# Unitbase_Keinz_2022.net
KiCad netlist of a schematic drawn in EAGLE
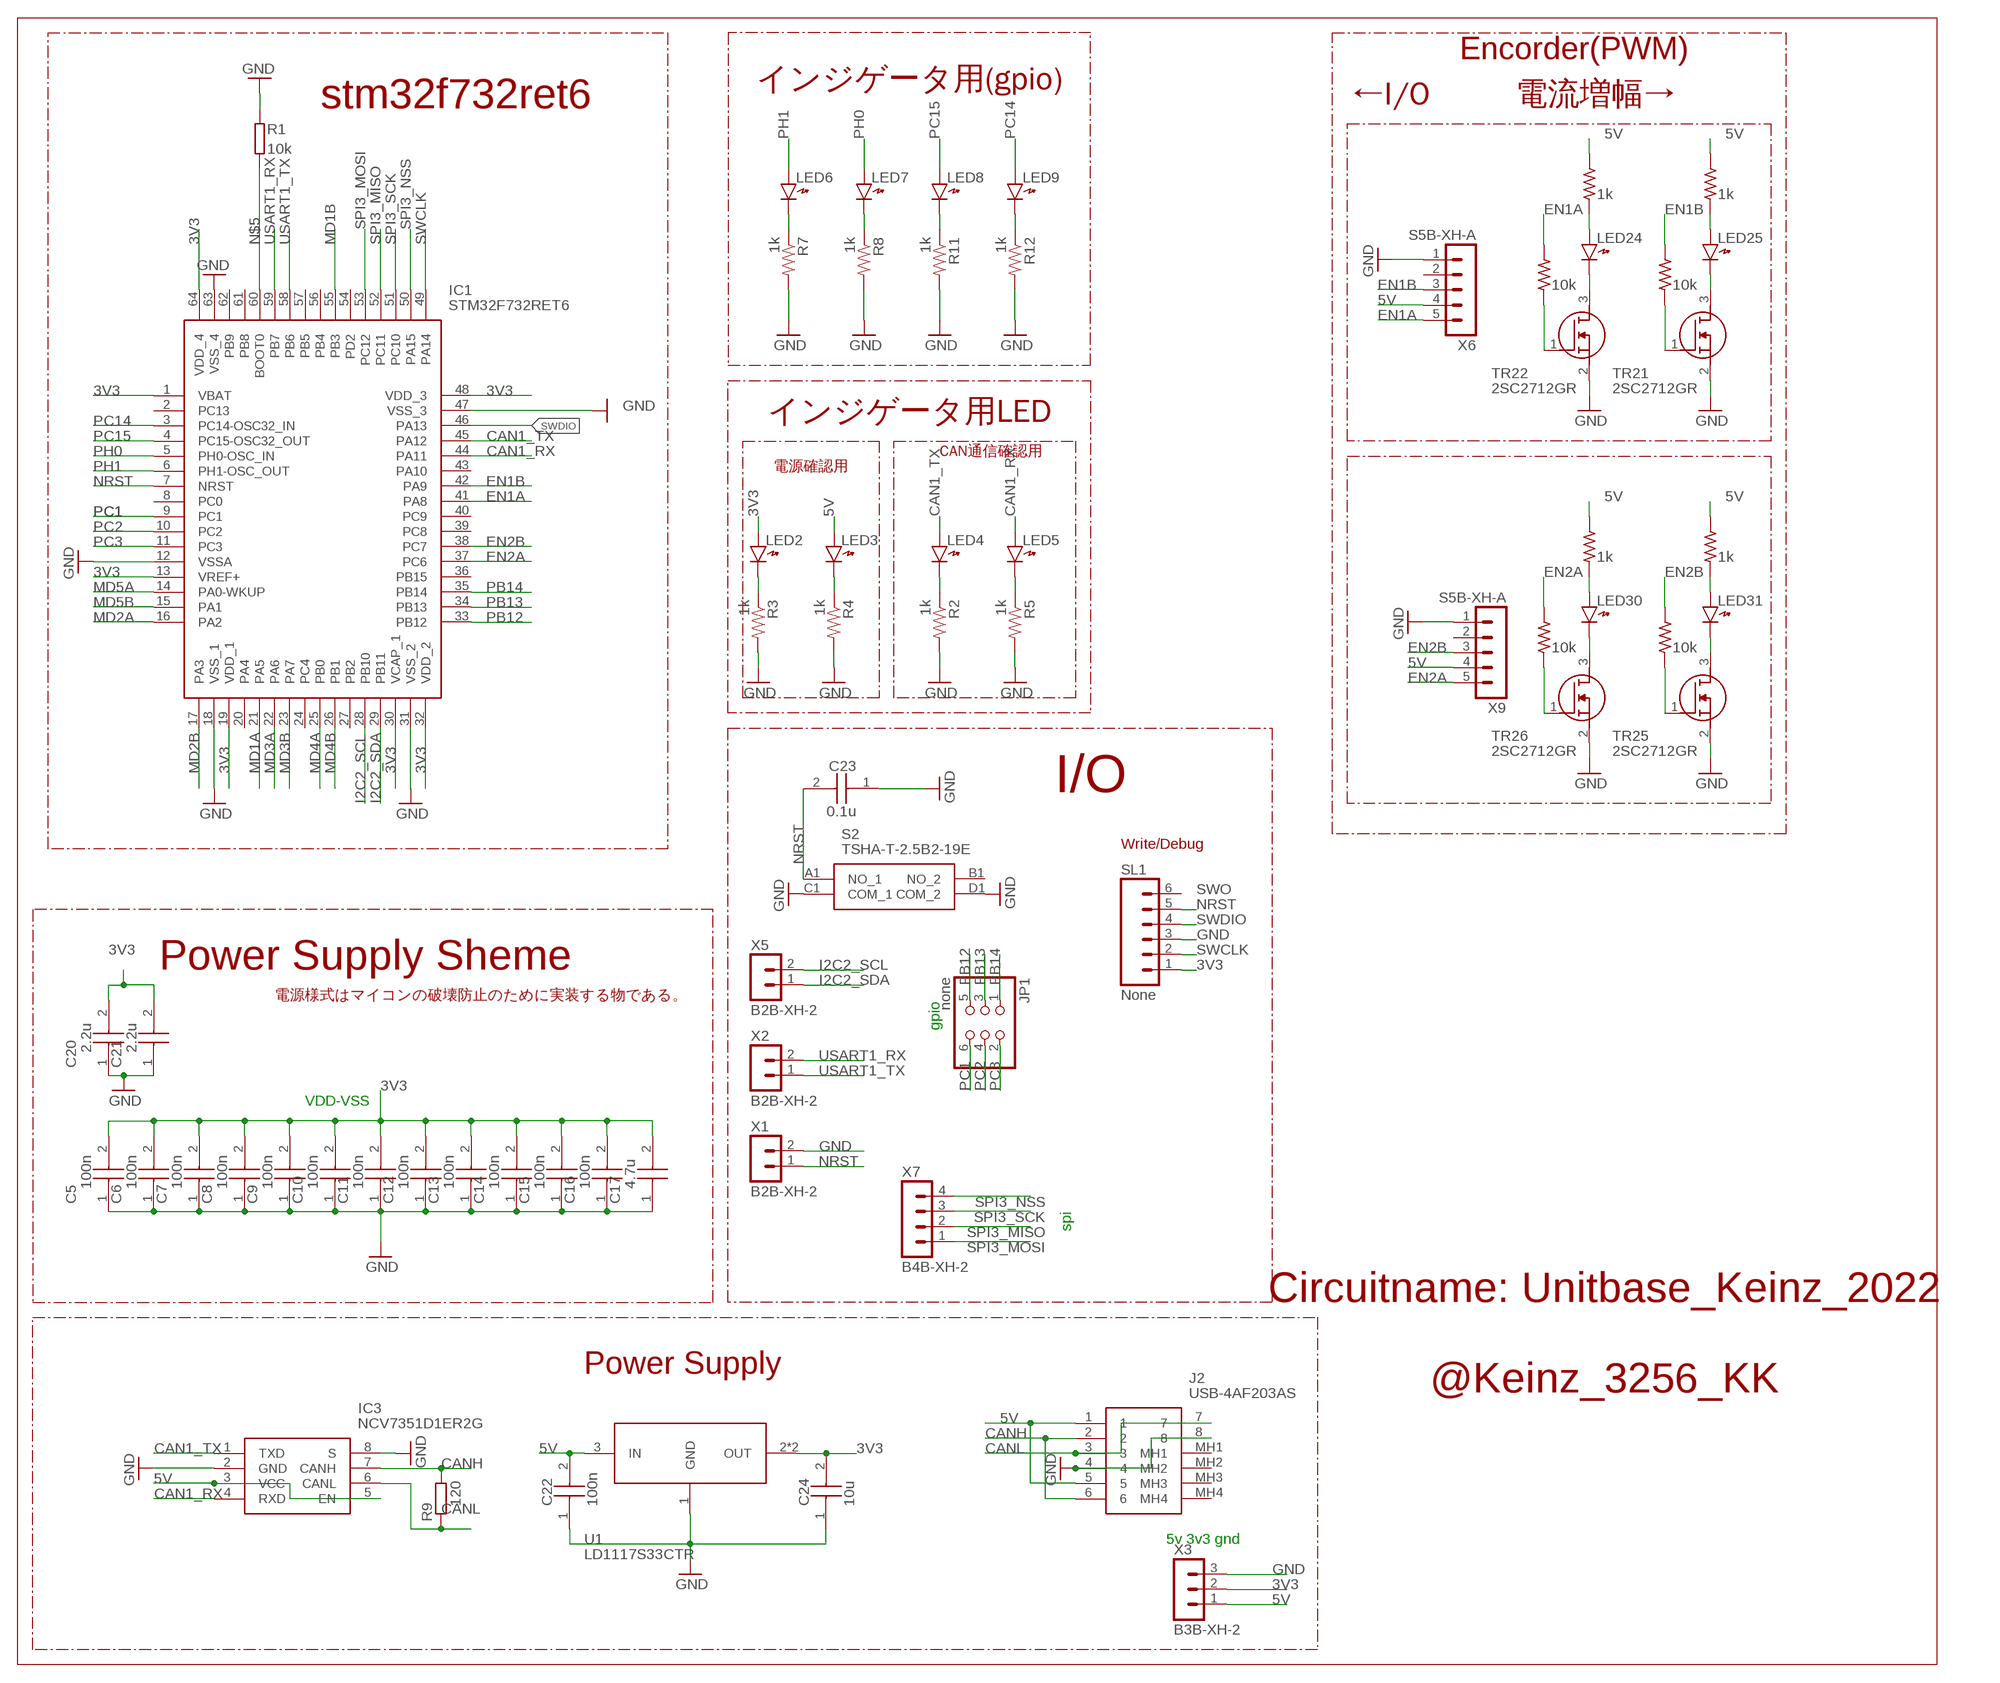
[diagram p0: schematic, sheet 1]
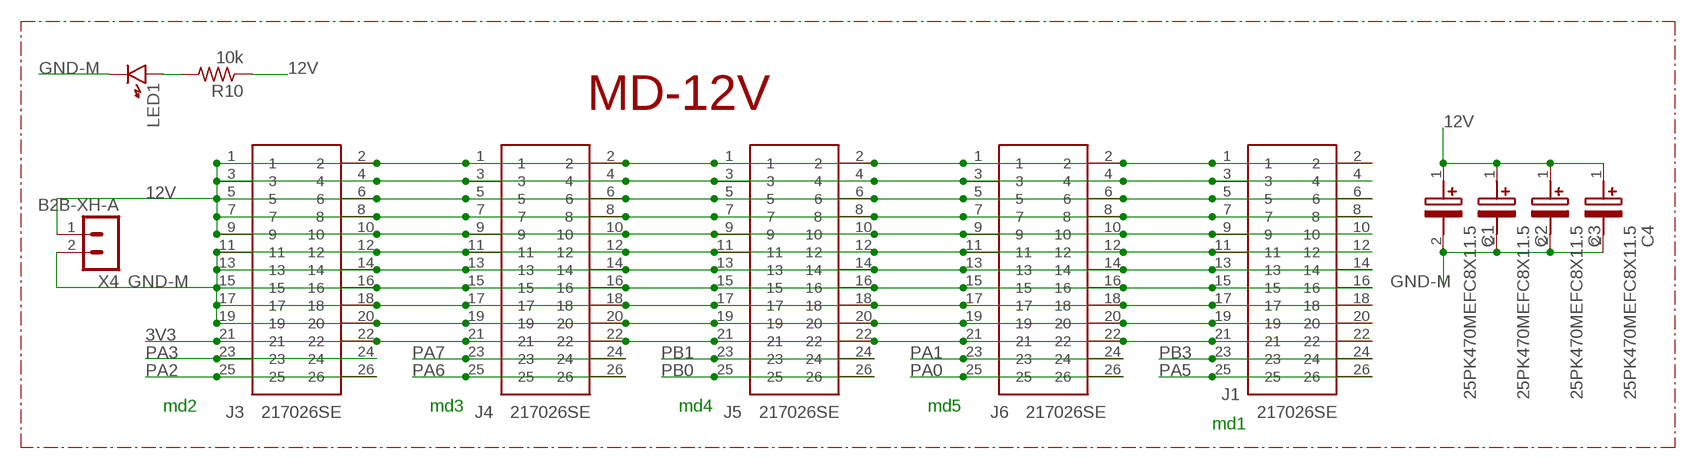
[diagram p1: schematic, sheet 2]
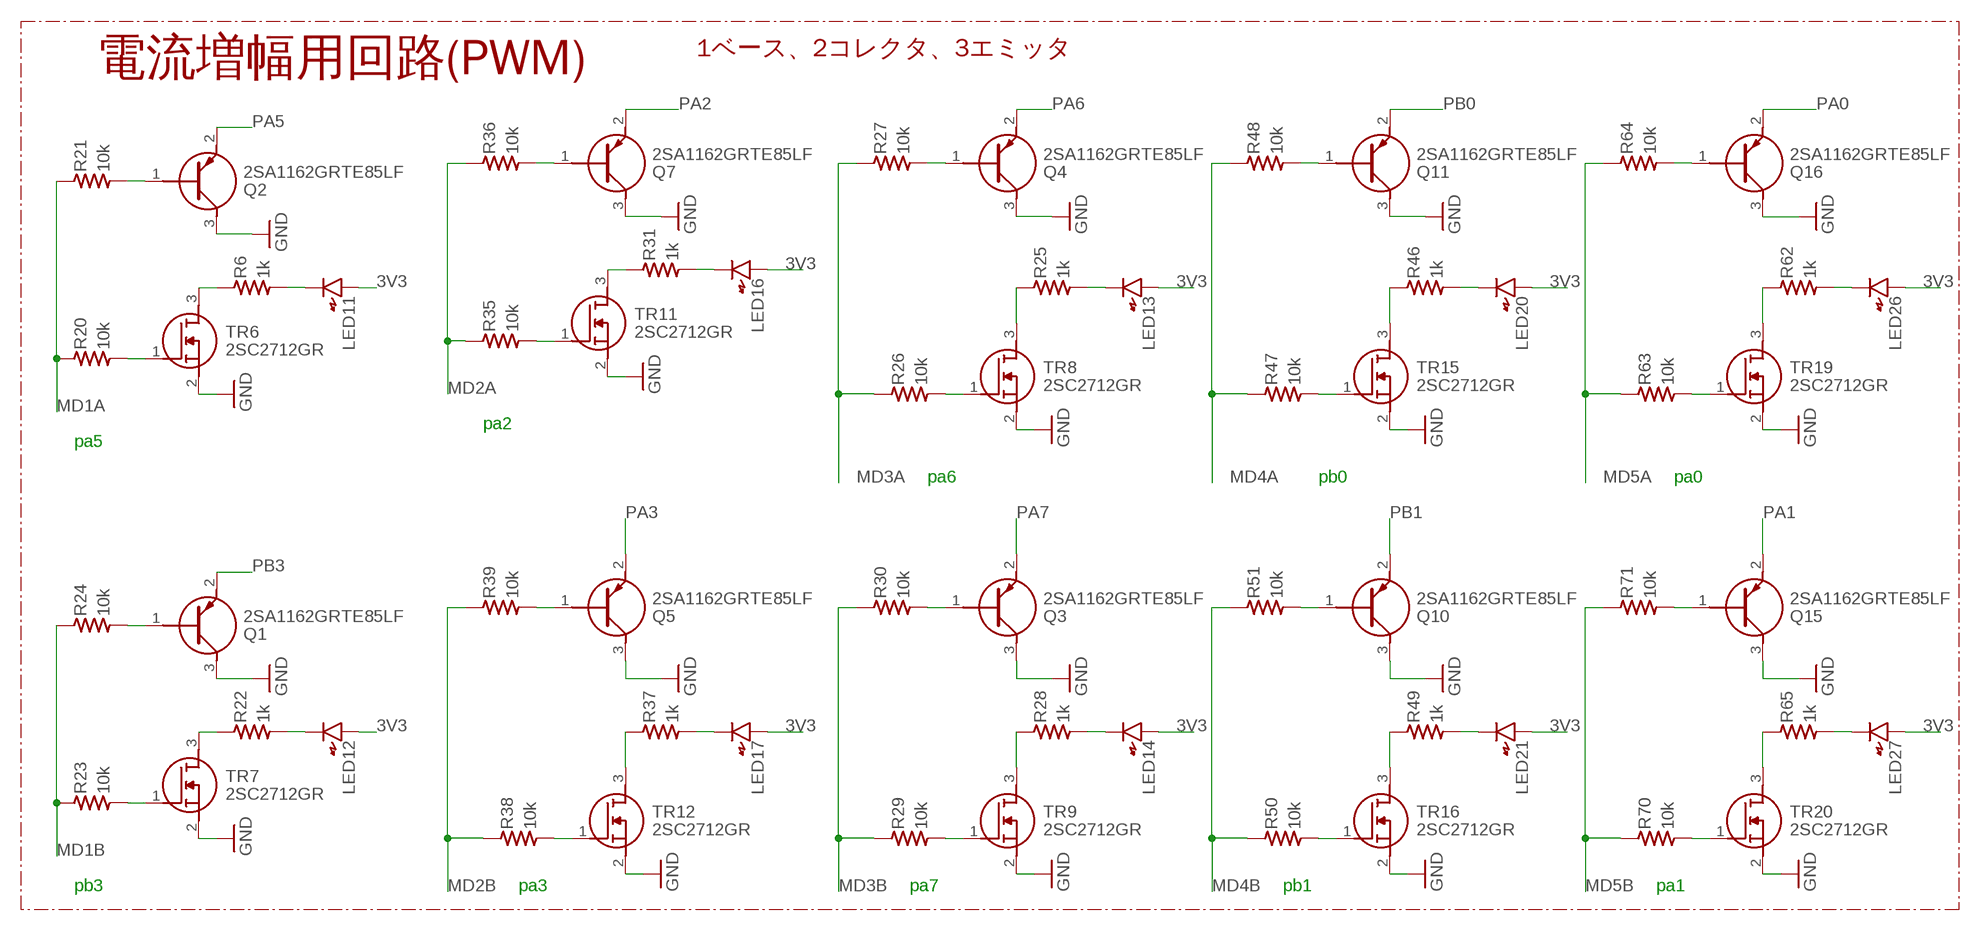
[diagram p2: schematic, sheet 3]

(export (version "E")
  (design (tool "Eeschema 10.0.6"))
  (components
    (comp (ref "C1")
      (value "25PK470MEFC8X11.5")
      (footprint "eagle-import:CAPPRD350W60D825H1150")
      (fields (field (name "MOUSER_PART_NUMBER") "232-25PK470MEFC8X115"))
      (libsource (lib "eagle-import") (part "25PK470MEFC8X11.5"))
    )
    (comp (ref "C2")
      (value "25PK470MEFC8X11.5")
      (footprint "eagle-import:CAPPRD350W60D825H1150")
      (fields (field (name "MOUSER_PART_NUMBER") "232-25PK470MEFC8X115"))
      (libsource (lib "eagle-import") (part "25PK470MEFC8X11.5"))
    )
    (comp (ref "C3")
      (value "25PK470MEFC8X11.5")
      (footprint "eagle-import:CAPPRD350W60D825H1150")
      (fields (field (name "MOUSER_PART_NUMBER") "232-25PK470MEFC8X115"))
      (libsource (lib "eagle-import") (part "25PK470MEFC8X11.5"))
    )
    (comp (ref "C4")
      (value "25PK470MEFC8X11.5")
      (footprint "eagle-import:CAPPRD350W60D825H1150")
      (fields (field (name "MOUSER_PART_NUMBER") "232-25PK470MEFC8X115"))
      (libsource (lib "eagle-import") (part "25PK470MEFC8X11.5"))
    )
    (comp (ref "J1")
      (value "217026SE")
      (footprint "eagle-import:217026SE")
      (libsource (lib "eagle-import") (part "217026SE"))
    )
    (comp (ref "J3")
      (value "217026SE")
      (footprint "eagle-import:217026SE")
      (libsource (lib "eagle-import") (part "217026SE"))
    )
    (comp (ref "J4")
      (value "217026SE")
      (footprint "eagle-import:217026SE")
      (libsource (lib "eagle-import") (part "217026SE"))
    )
    (comp (ref "J5")
      (value "217026SE")
      (footprint "eagle-import:217026SE")
      (libsource (lib "eagle-import") (part "217026SE"))
    )
    (comp (ref "J6")
      (value "217026SE")
      (footprint "eagle-import:217026SE")
      (libsource (lib "eagle-import") (part "217026SE"))
    )
    (comp (ref "LED1")
      (value "LED1608")
      (footprint "eagle-import:LED1608")
      (libsource (lib "eagle-import") (part "LED1608"))
    )
    (comp (ref "R10")
      (value "10k")
      (footprint "eagle-import:R0603")
      (libsource (lib "eagle-import") (part "R-US_R0603"))
    )
    (comp (ref "X4")
      (value "B2B-XH-A")
      (footprint "eagle-import:B2B-XH-A")
      (libsource (lib "eagle-import") (part "B2B-XH-A"))
    )
    (comp (ref "C5")
      (value "100n")
      (footprint "eagle-import:CAPC1709X100N")
      (fields
        (field (name "MANUFACTURER_PART_NUMBER") "AMK107BBJ476MA-RE")
        (field (name "MOUSER_PART_NUMBER") "963-AMK107BBJ476MARE")
        (field (name "RS_PART_NUMBER") "1843762P")
      )
      (libsource (lib "eagle-import") (part "AMK107BBJ476MA-RE"))
    )
    (comp (ref "C6")
      (value "100n")
      (footprint "eagle-import:CAPC1709X100N")
      (fields
        (field (name "MANUFACTURER_PART_NUMBER") "AMK107BBJ476MA-RE")
        (field (name "MOUSER_PART_NUMBER") "963-AMK107BBJ476MARE")
        (field (name "RS_PART_NUMBER") "1843762P")
      )
      (libsource (lib "eagle-import") (part "AMK107BBJ476MA-RE"))
    )
    (comp (ref "C7")
      (value "100n")
      (footprint "eagle-import:CAPC1709X100N")
      (fields
        (field (name "MANUFACTURER_PART_NUMBER") "AMK107BBJ476MA-RE")
        (field (name "MOUSER_PART_NUMBER") "963-AMK107BBJ476MARE")
        (field (name "RS_PART_NUMBER") "1843762P")
      )
      (libsource (lib "eagle-import") (part "AMK107BBJ476MA-RE"))
    )
    (comp (ref "C8")
      (value "100n")
      (footprint "eagle-import:CAPC1709X100N")
      (fields
        (field (name "MANUFACTURER_PART_NUMBER") "AMK107BBJ476MA-RE")
        (field (name "MOUSER_PART_NUMBER") "963-AMK107BBJ476MARE")
        (field (name "RS_PART_NUMBER") "1843762P")
      )
      (libsource (lib "eagle-import") (part "AMK107BBJ476MA-RE"))
    )
    (comp (ref "C9")
      (value "100n")
      (footprint "eagle-import:CAPC1709X100N")
      (fields
        (field (name "MANUFACTURER_PART_NUMBER") "AMK107BBJ476MA-RE")
        (field (name "MOUSER_PART_NUMBER") "963-AMK107BBJ476MARE")
        (field (name "RS_PART_NUMBER") "1843762P")
      )
      (libsource (lib "eagle-import") (part "AMK107BBJ476MA-RE"))
    )
    (comp (ref "C10")
      (value "100n")
      (footprint "eagle-import:CAPC1709X100N")
      (fields
        (field (name "MANUFACTURER_PART_NUMBER") "AMK107BBJ476MA-RE")
        (field (name "MOUSER_PART_NUMBER") "963-AMK107BBJ476MARE")
        (field (name "RS_PART_NUMBER") "1843762P")
      )
      (libsource (lib "eagle-import") (part "AMK107BBJ476MA-RE"))
    )
    (comp (ref "C11")
      (value "100n")
      (footprint "eagle-import:CAPC1709X100N")
      (fields
        (field (name "MANUFACTURER_PART_NUMBER") "AMK107BBJ476MA-RE")
        (field (name "MOUSER_PART_NUMBER") "963-AMK107BBJ476MARE")
        (field (name "RS_PART_NUMBER") "1843762P")
      )
      (libsource (lib "eagle-import") (part "AMK107BBJ476MA-RE"))
    )
    (comp (ref "C12")
      (value "100n")
      (footprint "eagle-import:CAPC1709X100N")
      (fields
        (field (name "MANUFACTURER_PART_NUMBER") "AMK107BBJ476MA-RE")
        (field (name "MOUSER_PART_NUMBER") "963-AMK107BBJ476MARE")
        (field (name "RS_PART_NUMBER") "1843762P")
      )
      (libsource (lib "eagle-import") (part "AMK107BBJ476MA-RE"))
    )
    (comp (ref "C13")
      (value "100n")
      (footprint "eagle-import:CAPC1709X100N")
      (fields
        (field (name "MANUFACTURER_PART_NUMBER") "AMK107BBJ476MA-RE")
        (field (name "MOUSER_PART_NUMBER") "963-AMK107BBJ476MARE")
        (field (name "RS_PART_NUMBER") "1843762P")
      )
      (libsource (lib "eagle-import") (part "AMK107BBJ476MA-RE"))
    )
    (comp (ref "C14")
      (value "100n")
      (footprint "eagle-import:CAPC1709X100N")
      (fields
        (field (name "MANUFACTURER_PART_NUMBER") "AMK107BBJ476MA-RE")
        (field (name "MOUSER_PART_NUMBER") "963-AMK107BBJ476MARE")
        (field (name "RS_PART_NUMBER") "1843762P")
      )
      (libsource (lib "eagle-import") (part "AMK107BBJ476MA-RE"))
    )
    (comp (ref "C15")
      (value "100n")
      (footprint "eagle-import:CAPC1709X100N")
      (fields
        (field (name "MANUFACTURER_PART_NUMBER") "AMK107BBJ476MA-RE")
        (field (name "MOUSER_PART_NUMBER") "963-AMK107BBJ476MARE")
        (field (name "RS_PART_NUMBER") "1843762P")
      )
      (libsource (lib "eagle-import") (part "AMK107BBJ476MA-RE"))
    )
    (comp (ref "C16")
      (value "100n")
      (footprint "eagle-import:CAPC1709X100N")
      (fields
        (field (name "MANUFACTURER_PART_NUMBER") "AMK107BBJ476MA-RE")
        (field (name "MOUSER_PART_NUMBER") "963-AMK107BBJ476MARE")
        (field (name "RS_PART_NUMBER") "1843762P")
      )
      (libsource (lib "eagle-import") (part "AMK107BBJ476MA-RE"))
    )
    (comp (ref "C17")
      (value "4.7u")
      (footprint "eagle-import:CAPC1709X100N")
      (fields
        (field (name "MANUFACTURER_PART_NUMBER") "AMK107BBJ476MA-RE")
        (field (name "MOUSER_PART_NUMBER") "963-AMK107BBJ476MARE")
        (field (name "RS_PART_NUMBER") "1843762P")
      )
      (libsource (lib "eagle-import") (part "AMK107BBJ476MA-RE"))
    )
    (comp (ref "C20")
      (value "2.2u")
      (footprint "eagle-import:CAPC1709X100N")
      (fields
        (field (name "MANUFACTURER_PART_NUMBER") "AMK107BBJ476MA-RE")
        (field (name "MOUSER_PART_NUMBER") "963-AMK107BBJ476MARE")
        (field (name "RS_PART_NUMBER") "1843762P")
      )
      (libsource (lib "eagle-import") (part "AMK107BBJ476MA-RE"))
    )
    (comp (ref "C21")
      (value "2.2u")
      (footprint "eagle-import:CAPC1709X100N")
      (fields
        (field (name "MANUFACTURER_PART_NUMBER") "AMK107BBJ476MA-RE")
        (field (name "MOUSER_PART_NUMBER") "963-AMK107BBJ476MARE")
        (field (name "RS_PART_NUMBER") "1843762P")
      )
      (libsource (lib "eagle-import") (part "AMK107BBJ476MA-RE"))
    )
    (comp (ref "C22")
      (value "100n")
      (footprint "eagle-import:CAPC1608X90N")
      (fields
        (field (name "MANUFACTURER_PART_NUMBER") "GRM188B31A106KE69D")
        (field (name "RS_PART_NUMBER") "8847157P")
      )
      (libsource (lib "eagle-import") (part "GRM188B31A106KE69D"))
    )
    (comp (ref "C23")
      (value "0.1u")
      (footprint "eagle-import:CAPC1709X100N")
      (fields
        (field (name "MANUFACTURER_PART_NUMBER") "AMK107BBJ476MA-RE")
        (field (name "MOUSER_PART_NUMBER") "963-AMK107BBJ476MARE")
        (field (name "RS_PART_NUMBER") "1843762P")
      )
      (libsource (lib "eagle-import") (part "AMK107BBJ476MA-RE"))
    )
    (comp (ref "C24")
      (value "10u")
      (footprint "eagle-import:CAPC1608X90N")
      (fields
        (field (name "MANUFACTURER_PART_NUMBER") "GRM188B31A106KE69D")
        (field (name "RS_PART_NUMBER") "8847157P")
      )
      (libsource (lib "eagle-import") (part "GRM188B31A106KE69D"))
    )
    (comp (ref "IC1")
      (value "STM32F732RET6")
      (footprint "eagle-import:QFP50P1200X1200X160-64N@1")
      (fields (field (name "MOUSER_PART_NUMBER") "511-STM32F732RET6"))
      (libsource (lib "eagle-import") (part "STM32F732RET6"))
    )
    (comp (ref "IC3")
      (value "NCV7351D1ER2G")
      (footprint "eagle-import:SOIC127P600X175-8N")
      (fields (field (name "MOUSER_PART_NUMBER") "863-NCV7351D1ER2G"))
      (libsource (lib "eagle-import") (part "NCV7351D1ER2G"))
    )
    (comp (ref "J2")
      (value "USB-4AF203AS")
      (footprint "eagle-import:USB4AF203AS")
      (libsource (lib "eagle-import") (part "USB-4AF203AS"))
    )
    (comp (ref "JP1")
      (value "none")
      (footprint "eagle-import:2X03")
      (libsource (lib "eagle-import") (part "PINHD-2X3"))
    )
    (comp (ref "LED2")
      (value "LED1608")
      (footprint "eagle-import:LED1608")
      (libsource (lib "eagle-import") (part "LED1608"))
    )
    (comp (ref "LED3")
      (value "LED1608")
      (footprint "eagle-import:LED1608")
      (libsource (lib "eagle-import") (part "LED1608"))
    )
    (comp (ref "LED4")
      (value "LED1608")
      (footprint "eagle-import:LED1608")
      (libsource (lib "eagle-import") (part "LED1608"))
    )
    (comp (ref "LED5")
      (value "LED1608")
      (footprint "eagle-import:LED1608")
      (libsource (lib "eagle-import") (part "LED1608"))
    )
    (comp (ref "LED6")
      (value "LED1608")
      (footprint "eagle-import:LED1608")
      (libsource (lib "eagle-import") (part "LED1608"))
    )
    (comp (ref "LED7")
      (value "LED1608")
      (footprint "eagle-import:LED1608")
      (libsource (lib "eagle-import") (part "LED1608"))
    )
    (comp (ref "LED8")
      (value "LED1608")
      (footprint "eagle-import:LED1608")
      (libsource (lib "eagle-import") (part "LED1608"))
    )
    (comp (ref "LED9")
      (value "LED1608")
      (footprint "eagle-import:LED1608")
      (libsource (lib "eagle-import") (part "LED1608"))
    )
    (comp (ref "LED24")
      (value "LED1608")
      (footprint "eagle-import:LED1608")
      (libsource (lib "eagle-import") (part "LED1608"))
    )
    (comp (ref "LED25")
      (value "LED1608")
      (footprint "eagle-import:LED1608")
      (libsource (lib "eagle-import") (part "LED1608"))
    )
    (comp (ref "LED30")
      (value "LED1608")
      (footprint "eagle-import:LED1608")
      (libsource (lib "eagle-import") (part "LED1608"))
    )
    (comp (ref "LED31")
      (value "LED1608")
      (footprint "eagle-import:LED1608")
      (libsource (lib "eagle-import") (part "LED1608"))
    )
    (comp (ref "R1")
      (value "10k")
      (footprint "eagle-import:SMD1608")
      (libsource (lib "eagle-import") (part "RESISTOR1608"))
    )
    (comp (ref "R2")
      (value "1k")
      (footprint "eagle-import:R0603")
      (libsource (lib "eagle-import") (part "R-US_R0603"))
    )
    (comp (ref "R3")
      (value "1k")
      (footprint "eagle-import:R0603")
      (libsource (lib "eagle-import") (part "R-US_R0603"))
    )
    (comp (ref "R4")
      (value "1k")
      (footprint "eagle-import:R0603")
      (libsource (lib "eagle-import") (part "R-US_R0603"))
    )
    (comp (ref "R5")
      (value "1k")
      (footprint "eagle-import:R0603")
      (libsource (lib "eagle-import") (part "R-US_R0603"))
    )
    (comp (ref "R7")
      (value "1k")
      (footprint "eagle-import:R0603")
      (libsource (lib "eagle-import") (part "R-US_R0603"))
    )
    (comp (ref "R8")
      (value "1k")
      (footprint "eagle-import:R0603")
      (libsource (lib "eagle-import") (part "R-US_R0603"))
    )
    (comp (ref "R9")
      (value "120")
      (footprint "eagle-import:1608")
      (libsource (lib "eagle-import") (part "R1608"))
    )
    (comp (ref "R11")
      (value "1k")
      (footprint "eagle-import:R0603")
      (libsource (lib "eagle-import") (part "R-US_R0603"))
    )
    (comp (ref "R12")
      (value "1k")
      (footprint "eagle-import:R0603")
      (libsource (lib "eagle-import") (part "R-US_R0603"))
    )
    (comp (ref "R54")
      (value "10k")
      (footprint "eagle-import:SMD1608")
      (libsource (lib "eagle-import") (part "RESISTOR-US1608"))
    )
    (comp (ref "R59")
      (value "1k")
      (footprint "eagle-import:SMD1608")
      (libsource (lib "eagle-import") (part "RESISTOR-US1608"))
    )
    (comp (ref "R60")
      (value "10k")
      (footprint "eagle-import:SMD1608")
      (libsource (lib "eagle-import") (part "RESISTOR-US1608"))
    )
    (comp (ref "R61")
      (value "1k")
      (footprint "eagle-import:SMD1608")
      (libsource (lib "eagle-import") (part "RESISTOR-US1608"))
    )
    (comp (ref "R66")
      (value "10k")
      (footprint "eagle-import:SMD1608")
      (libsource (lib "eagle-import") (part "RESISTOR-US1608"))
    )
    (comp (ref "R67")
      (value "1k")
      (footprint "eagle-import:SMD1608")
      (libsource (lib "eagle-import") (part "RESISTOR-US1608"))
    )
    (comp (ref "R68")
      (value "10k")
      (footprint "eagle-import:SMD1608")
      (libsource (lib "eagle-import") (part "RESISTOR-US1608"))
    )
    (comp (ref "R69")
      (value "1k")
      (footprint "eagle-import:SMD1608")
      (libsource (lib "eagle-import") (part "RESISTOR-US1608"))
    )
    (comp (ref "S2")
      (value "TSHA-T-2.5B2-19E")
      (footprint "eagle-import:TSHAT25B219E")
      (libsource (lib "eagle-import") (part "TSHA-T-2.5B2-19E"))
    )
    (comp (ref "SL1")
      (value "None")
      (footprint "eagle-import:06PA")
      (libsource (lib "eagle-import") (part "MA06"))
    )
    (comp (ref "TR21")
      (value "2SC2712GR")
      (footprint "eagle-import:SOT-23")
      (libsource (lib "eagle-import") (part "SOT-23_NMOS"))
    )
    (comp (ref "TR22")
      (value "2SC2712GR")
      (footprint "eagle-import:SOT-23")
      (libsource (lib "eagle-import") (part "SOT-23_NMOS"))
    )
    (comp (ref "TR25")
      (value "2SC2712GR")
      (footprint "eagle-import:SOT-23")
      (libsource (lib "eagle-import") (part "SOT-23_NMOS"))
    )
    (comp (ref "TR26")
      (value "2SC2712GR")
      (footprint "eagle-import:SOT-23")
      (libsource (lib "eagle-import") (part "SOT-23_NMOS"))
    )
    (comp (ref "U1")
      (value "LD1117S33CTR")
      (footprint "eagle-import:SOT223")
      (fields (field (name "MF") "STMicroelectronics"))
      (libsource (lib "eagle-import") (part "LD1117S33CTR"))
    )
    (comp (ref "X1")
      (value "B2B-XH-2")
      (footprint "eagle-import:B2B-XH-A")
      (libsource (lib "eagle-import") (part "B2B-XH-2"))
    )
    (comp (ref "X2")
      (value "B2B-XH-2")
      (footprint "eagle-import:B2B-XH-A")
      (libsource (lib "eagle-import") (part "B2B-XH-2"))
    )
    (comp (ref "X3")
      (value "B3B-XH-2")
      (footprint "eagle-import:B3B-XH-A")
      (libsource (lib "eagle-import") (part "B3B-XH-2"))
    )
    (comp (ref "X5")
      (value "B2B-XH-2")
      (footprint "eagle-import:B2B-XH-A")
      (libsource (lib "eagle-import") (part "B2B-XH-2"))
    )
    (comp (ref "X6")
      (value "S5B-XH-A")
      (footprint "eagle-import:S5B-XH-A")
      (libsource (lib "eagle-import") (part "S5B-XH-A"))
    )
    (comp (ref "X7")
      (value "B4B-XH-2")
      (footprint "eagle-import:B4B-XH-A")
      (libsource (lib "eagle-import") (part "B4B-XH-2"))
    )
    (comp (ref "X9")
      (value "S5B-XH-A")
      (footprint "eagle-import:S5B-XH-A")
      (libsource (lib "eagle-import") (part "S5B-XH-A"))
    )
    (comp (ref "LED11")
      (value "LED1608")
      (footprint "eagle-import:LED1608")
      (libsource (lib "eagle-import") (part "LED1608"))
    )
    (comp (ref "LED12")
      (value "LED1608")
      (footprint "eagle-import:LED1608")
      (libsource (lib "eagle-import") (part "LED1608"))
    )
    (comp (ref "LED13")
      (value "LED1608")
      (footprint "eagle-import:LED1608")
      (libsource (lib "eagle-import") (part "LED1608"))
    )
    (comp (ref "LED14")
      (value "LED1608")
      (footprint "eagle-import:LED1608")
      (libsource (lib "eagle-import") (part "LED1608"))
    )
    (comp (ref "LED16")
      (value "LED1608")
      (footprint "eagle-import:LED1608")
      (libsource (lib "eagle-import") (part "LED1608"))
    )
    (comp (ref "LED17")
      (value "LED1608")
      (footprint "eagle-import:LED1608")
      (libsource (lib "eagle-import") (part "LED1608"))
    )
    (comp (ref "LED20")
      (value "LED1608")
      (footprint "eagle-import:LED1608")
      (libsource (lib "eagle-import") (part "LED1608"))
    )
    (comp (ref "LED21")
      (value "LED1608")
      (footprint "eagle-import:LED1608")
      (libsource (lib "eagle-import") (part "LED1608"))
    )
    (comp (ref "LED26")
      (value "LED1608")
      (footprint "eagle-import:LED1608")
      (libsource (lib "eagle-import") (part "LED1608"))
    )
    (comp (ref "LED27")
      (value "LED1608")
      (footprint "eagle-import:LED1608")
      (libsource (lib "eagle-import") (part "LED1608"))
    )
    (comp (ref "Q1")
      (value "2SA1162GRTE85LF")
      (footprint "eagle-import:2SA1162GRTE85LF")
      (libsource (lib "eagle-import") (part "2SA1162GRTE85LF"))
    )
    (comp (ref "Q2")
      (value "2SA1162GRTE85LF")
      (footprint "eagle-import:2SA1162GRTE85LF")
      (libsource (lib "eagle-import") (part "2SA1162GRTE85LF"))
    )
    (comp (ref "Q3")
      (value "2SA1162GRTE85LF")
      (footprint "eagle-import:2SA1162GRTE85LF")
      (libsource (lib "eagle-import") (part "2SA1162GRTE85LF"))
    )
    (comp (ref "Q4")
      (value "2SA1162GRTE85LF")
      (footprint "eagle-import:2SA1162GRTE85LF")
      (libsource (lib "eagle-import") (part "2SA1162GRTE85LF"))
    )
    (comp (ref "Q5")
      (value "2SA1162GRTE85LF")
      (footprint "eagle-import:2SA1162GRTE85LF")
      (libsource (lib "eagle-import") (part "2SA1162GRTE85LF"))
    )
    (comp (ref "Q7")
      (value "2SA1162GRTE85LF")
      (footprint "eagle-import:2SA1162GRTE85LF")
      (libsource (lib "eagle-import") (part "2SA1162GRTE85LF"))
    )
    (comp (ref "Q10")
      (value "2SA1162GRTE85LF")
      (footprint "eagle-import:2SA1162GRTE85LF")
      (libsource (lib "eagle-import") (part "2SA1162GRTE85LF"))
    )
    (comp (ref "Q11")
      (value "2SA1162GRTE85LF")
      (footprint "eagle-import:2SA1162GRTE85LF")
      (libsource (lib "eagle-import") (part "2SA1162GRTE85LF"))
    )
    (comp (ref "Q15")
      (value "2SA1162GRTE85LF")
      (footprint "eagle-import:2SA1162GRTE85LF")
      (libsource (lib "eagle-import") (part "2SA1162GRTE85LF"))
    )
    (comp (ref "Q16")
      (value "2SA1162GRTE85LF")
      (footprint "eagle-import:2SA1162GRTE85LF")
      (libsource (lib "eagle-import") (part "2SA1162GRTE85LF"))
    )
    (comp (ref "R6")
      (value "1k")
      (footprint "eagle-import:SMD1608")
      (libsource (lib "eagle-import") (part "RESISTOR-US1608"))
    )
    (comp (ref "R20")
      (value "10k")
      (footprint "eagle-import:SMD1608")
      (libsource (lib "eagle-import") (part "RESISTOR-US1608"))
    )
    (comp (ref "R21")
      (value "10k")
      (footprint "eagle-import:SMD1608")
      (libsource (lib "eagle-import") (part "RESISTOR-US1608"))
    )
    (comp (ref "R22")
      (value "1k")
      (footprint "eagle-import:SMD1608")
      (libsource (lib "eagle-import") (part "RESISTOR-US1608"))
    )
    (comp (ref "R23")
      (value "10k")
      (footprint "eagle-import:SMD1608")
      (libsource (lib "eagle-import") (part "RESISTOR-US1608"))
    )
    (comp (ref "R24")
      (value "10k")
      (footprint "eagle-import:SMD1608")
      (libsource (lib "eagle-import") (part "RESISTOR-US1608"))
    )
    (comp (ref "R25")
      (value "1k")
      (footprint "eagle-import:SMD1608")
      (libsource (lib "eagle-import") (part "RESISTOR-US1608"))
    )
    (comp (ref "R26")
      (value "10k")
      (footprint "eagle-import:SMD1608")
      (libsource (lib "eagle-import") (part "RESISTOR-US1608"))
    )
    (comp (ref "R27")
      (value "10k")
      (footprint "eagle-import:SMD1608")
      (libsource (lib "eagle-import") (part "RESISTOR-US1608"))
    )
    (comp (ref "R28")
      (value "1k")
      (footprint "eagle-import:SMD1608")
      (libsource (lib "eagle-import") (part "RESISTOR-US1608"))
    )
    (comp (ref "R29")
      (value "10k")
      (footprint "eagle-import:SMD1608")
      (libsource (lib "eagle-import") (part "RESISTOR-US1608"))
    )
    (comp (ref "R30")
      (value "10k")
      (footprint "eagle-import:SMD1608")
      (libsource (lib "eagle-import") (part "RESISTOR-US1608"))
    )
    (comp (ref "R31")
      (value "1k")
      (footprint "eagle-import:SMD1608")
      (libsource (lib "eagle-import") (part "RESISTOR-US1608"))
    )
    (comp (ref "R35")
      (value "10k")
      (footprint "eagle-import:SMD1608")
      (libsource (lib "eagle-import") (part "RESISTOR-US1608"))
    )
    (comp (ref "R36")
      (value "10k")
      (footprint "eagle-import:SMD1608")
      (libsource (lib "eagle-import") (part "RESISTOR-US1608"))
    )
    (comp (ref "R37")
      (value "1k")
      (footprint "eagle-import:SMD1608")
      (libsource (lib "eagle-import") (part "RESISTOR-US1608"))
    )
    (comp (ref "R38")
      (value "10k")
      (footprint "eagle-import:SMD1608")
      (libsource (lib "eagle-import") (part "RESISTOR-US1608"))
    )
    (comp (ref "R39")
      (value "10k")
      (footprint "eagle-import:SMD1608")
      (libsource (lib "eagle-import") (part "RESISTOR-US1608"))
    )
    (comp (ref "R46")
      (value "1k")
      (footprint "eagle-import:SMD1608")
      (libsource (lib "eagle-import") (part "RESISTOR-US1608"))
    )
    (comp (ref "R47")
      (value "10k")
      (footprint "eagle-import:SMD1608")
      (libsource (lib "eagle-import") (part "RESISTOR-US1608"))
    )
    (comp (ref "R48")
      (value "10k")
      (footprint "eagle-import:SMD1608")
      (libsource (lib "eagle-import") (part "RESISTOR-US1608"))
    )
    (comp (ref "R49")
      (value "1k")
      (footprint "eagle-import:SMD1608")
      (libsource (lib "eagle-import") (part "RESISTOR-US1608"))
    )
    (comp (ref "R50")
      (value "10k")
      (footprint "eagle-import:SMD1608")
      (libsource (lib "eagle-import") (part "RESISTOR-US1608"))
    )
    (comp (ref "R51")
      (value "10k")
      (footprint "eagle-import:SMD1608")
      (libsource (lib "eagle-import") (part "RESISTOR-US1608"))
    )
    (comp (ref "R62")
      (value "1k")
      (footprint "eagle-import:SMD1608")
      (libsource (lib "eagle-import") (part "RESISTOR-US1608"))
    )
    (comp (ref "R63")
      (value "10k")
      (footprint "eagle-import:SMD1608")
      (libsource (lib "eagle-import") (part "RESISTOR-US1608"))
    )
    (comp (ref "R64")
      (value "10k")
      (footprint "eagle-import:SMD1608")
      (libsource (lib "eagle-import") (part "RESISTOR-US1608"))
    )
    (comp (ref "R65")
      (value "1k")
      (footprint "eagle-import:SMD1608")
      (libsource (lib "eagle-import") (part "RESISTOR-US1608"))
    )
    (comp (ref "R70")
      (value "10k")
      (footprint "eagle-import:SMD1608")
      (libsource (lib "eagle-import") (part "RESISTOR-US1608"))
    )
    (comp (ref "R71")
      (value "10k")
      (footprint "eagle-import:SMD1608")
      (libsource (lib "eagle-import") (part "RESISTOR-US1608"))
    )
    (comp (ref "TR6")
      (value "2SC2712GR")
      (footprint "eagle-import:SOT-23")
      (libsource (lib "eagle-import") (part "SOT-23_NMOS"))
    )
    (comp (ref "TR7")
      (value "2SC2712GR")
      (footprint "eagle-import:SOT-23")
      (libsource (lib "eagle-import") (part "SOT-23_NMOS"))
    )
    (comp (ref "TR8")
      (value "2SC2712GR")
      (footprint "eagle-import:SOT-23")
      (libsource (lib "eagle-import") (part "SOT-23_NMOS"))
    )
    (comp (ref "TR9")
      (value "2SC2712GR")
      (footprint "eagle-import:SOT-23")
      (libsource (lib "eagle-import") (part "SOT-23_NMOS"))
    )
    (comp (ref "TR11")
      (value "2SC2712GR")
      (footprint "eagle-import:SOT-23")
      (libsource (lib "eagle-import") (part "SOT-23_NMOS"))
    )
    (comp (ref "TR12")
      (value "2SC2712GR")
      (footprint "eagle-import:SOT-23")
      (libsource (lib "eagle-import") (part "SOT-23_NMOS"))
    )
    (comp (ref "TR15")
      (value "2SC2712GR")
      (footprint "eagle-import:SOT-23")
      (libsource (lib "eagle-import") (part "SOT-23_NMOS"))
    )
    (comp (ref "TR16")
      (value "2SC2712GR")
      (footprint "eagle-import:SOT-23")
      (libsource (lib "eagle-import") (part "SOT-23_NMOS"))
    )
    (comp (ref "TR19")
      (value "2SC2712GR")
      (footprint "eagle-import:SOT-23")
      (libsource (lib "eagle-import") (part "SOT-23_NMOS"))
    )
    (comp (ref "TR20")
      (value "2SC2712GR")
      (footprint "eagle-import:SOT-23")
      (libsource (lib "eagle-import") (part "SOT-23_NMOS"))
    )
  )
  (nets
    (net (code "1") (name "3V3") (class "Default")
      (node (ref "C10") (pin "2") (pinfunction "2_2") (pintype "bidirectional"))
      (node (ref "C11") (pin "2") (pinfunction "2_2") (pintype "bidirectional"))
      (node (ref "C12") (pin "2") (pinfunction "2_2") (pintype "bidirectional"))
      (node (ref "C13") (pin "2") (pinfunction "2_2") (pintype "bidirectional"))
      (node (ref "C14") (pin "2") (pinfunction "2_2") (pintype "bidirectional"))
      (node (ref "C15") (pin "2") (pinfunction "2_2") (pintype "bidirectional"))
      (node (ref "C16") (pin "2") (pinfunction "2_2") (pintype "bidirectional"))
      (node (ref "C17") (pin "2") (pinfunction "2_2") (pintype "bidirectional"))
      (node (ref "C20") (pin "2") (pinfunction "2_2") (pintype "bidirectional"))
      (node (ref "C21") (pin "2") (pinfunction "2_2") (pintype "bidirectional"))
      (node (ref "C24") (pin "2") (pinfunction "2_2") (pintype "bidirectional"))
      (node (ref "C5") (pin "2") (pinfunction "2_2") (pintype "bidirectional"))
      (node (ref "C6") (pin "2") (pinfunction "2_2") (pintype "bidirectional"))
      (node (ref "C7") (pin "2") (pinfunction "2_2") (pintype "bidirectional"))
      (node (ref "C8") (pin "2") (pinfunction "2_2") (pintype "bidirectional"))
      (node (ref "C9") (pin "2") (pinfunction "2_2") (pintype "bidirectional"))
      (node (ref "IC1") (pin "1") (pinfunction "VBAT_1") (pintype "power_in"))
      (node (ref "IC1") (pin "13") (pinfunction "VREF+_13") (pintype "power_in"))
      (node (ref "IC1") (pin "19") (pinfunction "VDD_1_19") (pintype "power_in"))
      (node (ref "IC1") (pin "30") (pinfunction "VCAP_1_30") (pintype "power_in"))
      (node (ref "IC1") (pin "32") (pinfunction "VDD_2_32") (pintype "power_in"))
      (node (ref "IC1") (pin "48") (pinfunction "VDD_3_48") (pintype "power_in"))
      (node (ref "IC1") (pin "64") (pinfunction "VDD_4_64") (pintype "power_in"))
      (node (ref "J1") (pin "21") (pinfunction "21_21") (pintype "bidirectional"))
      (node (ref "J1") (pin "22") (pinfunction "22_22") (pintype "bidirectional"))
      (node (ref "J3") (pin "21") (pinfunction "21_21") (pintype "bidirectional"))
      (node (ref "J3") (pin "22") (pinfunction "22_22") (pintype "bidirectional"))
      (node (ref "J4") (pin "21") (pinfunction "21_21") (pintype "bidirectional"))
      (node (ref "J4") (pin "22") (pinfunction "22_22") (pintype "bidirectional"))
      (node (ref "J5") (pin "21") (pinfunction "21_21") (pintype "bidirectional"))
      (node (ref "J5") (pin "22") (pinfunction "22_22") (pintype "bidirectional"))
      (node (ref "J6") (pin "21") (pinfunction "21_21") (pintype "bidirectional"))
      (node (ref "J6") (pin "22") (pinfunction "22_22") (pintype "bidirectional"))
      (node (ref "LED11") (pin "A") (pinfunction "A_A") (pintype "passive"))
      (node (ref "LED12") (pin "A") (pinfunction "A_A") (pintype "passive"))
      (node (ref "LED13") (pin "A") (pinfunction "A_A") (pintype "passive"))
      (node (ref "LED14") (pin "A") (pinfunction "A_A") (pintype "passive"))
      (node (ref "LED16") (pin "A") (pinfunction "A_A") (pintype "passive"))
      (node (ref "LED17") (pin "A") (pinfunction "A_A") (pintype "passive"))
      (node (ref "LED2") (pin "A") (pinfunction "A_A") (pintype "passive"))
      (node (ref "LED20") (pin "A") (pinfunction "A_A") (pintype "passive"))
      (node (ref "LED21") (pin "A") (pinfunction "A_A") (pintype "passive"))
      (node (ref "LED26") (pin "A") (pinfunction "A_A") (pintype "passive"))
      (node (ref "LED27") (pin "A") (pinfunction "A_A") (pintype "passive"))
      (node (ref "SL1") (pin "1") (pinfunction "1_1") (pintype "passive"))
      (node (ref "U1") (pin "2") (pinfunction "OUT_2") (pintype "output"))
      (node (ref "U1") (pin "4") (pinfunction "OUT_4") (pintype "output"))
      (node (ref "X3") (pin "2") (pinfunction "2_2") (pintype "passive"))
    )
    (net (code "2") (name "5V") (class "Default")
      (node (ref "C22") (pin "2") (pinfunction "2_2") (pintype "bidirectional"))
      (node (ref "IC3") (pin "3") (pinfunction "VCC_3") (pintype "bidirectional"))
      (node (ref "IC3") (pin "5") (pinfunction "EN_5") (pintype "bidirectional"))
      (node (ref "J2") (pin "1") (pinfunction "1_1") (pintype "bidirectional"))
      (node (ref "J2") (pin "5") (pinfunction "5_5") (pintype "bidirectional"))
      (node (ref "LED3") (pin "A") (pinfunction "A_A") (pintype "passive"))
      (node (ref "R59") (pin "1") (pinfunction "1_1") (pintype "passive"))
      (node (ref "R61") (pin "1") (pinfunction "1_1") (pintype "passive"))
      (node (ref "R67") (pin "1") (pinfunction "1_1") (pintype "passive"))
      (node (ref "R69") (pin "1") (pinfunction "1_1") (pintype "passive"))
      (node (ref "U1") (pin "3") (pinfunction "IN_3") (pintype "input"))
      (node (ref "X3") (pin "1") (pinfunction "1_1") (pintype "passive"))
      (node (ref "X6") (pin "4") (pinfunction "4_4") (pintype "passive"))
      (node (ref "X9") (pin "4") (pinfunction "4_4") (pintype "passive"))
    )
    (net (code "3") (name "12V") (class "Default")
      (node (ref "C1") (pin "1") (pinfunction "+_1") (pintype "bidirectional"))
      (node (ref "C2") (pin "1") (pinfunction "+_1") (pintype "bidirectional"))
      (node (ref "C3") (pin "1") (pinfunction "+_1") (pintype "bidirectional"))
      (node (ref "C4") (pin "1") (pinfunction "+_1") (pintype "bidirectional"))
      (node (ref "J1") (pin "1") (pinfunction "1_1") (pintype "bidirectional"))
      (node (ref "J1") (pin "10") (pinfunction "10_10") (pintype "bidirectional"))
      (node (ref "J1") (pin "2") (pinfunction "2_2") (pintype "bidirectional"))
      (node (ref "J1") (pin "3") (pinfunction "3_3") (pintype "bidirectional"))
      (node (ref "J1") (pin "4") (pinfunction "4_4") (pintype "bidirectional"))
      (node (ref "J1") (pin "5") (pinfunction "5_5") (pintype "bidirectional"))
      (node (ref "J1") (pin "6") (pinfunction "6_6") (pintype "bidirectional"))
      (node (ref "J1") (pin "7") (pinfunction "7_7") (pintype "bidirectional"))
      (node (ref "J1") (pin "8") (pinfunction "8_8") (pintype "bidirectional"))
      (node (ref "J1") (pin "9") (pinfunction "9_9") (pintype "bidirectional"))
      (node (ref "J3") (pin "1") (pinfunction "1_1") (pintype "bidirectional"))
      (node (ref "J3") (pin "10") (pinfunction "10_10") (pintype "bidirectional"))
      (node (ref "J3") (pin "2") (pinfunction "2_2") (pintype "bidirectional"))
      (node (ref "J3") (pin "3") (pinfunction "3_3") (pintype "bidirectional"))
      (node (ref "J3") (pin "4") (pinfunction "4_4") (pintype "bidirectional"))
      (node (ref "J3") (pin "5") (pinfunction "5_5") (pintype "bidirectional"))
      (node (ref "J3") (pin "6") (pinfunction "6_6") (pintype "bidirectional"))
      (node (ref "J3") (pin "7") (pinfunction "7_7") (pintype "bidirectional"))
      (node (ref "J3") (pin "8") (pinfunction "8_8") (pintype "bidirectional"))
      (node (ref "J3") (pin "9") (pinfunction "9_9") (pintype "bidirectional"))
      (node (ref "J4") (pin "1") (pinfunction "1_1") (pintype "bidirectional"))
      (node (ref "J4") (pin "10") (pinfunction "10_10") (pintype "bidirectional"))
      (node (ref "J4") (pin "2") (pinfunction "2_2") (pintype "bidirectional"))
      (node (ref "J4") (pin "3") (pinfunction "3_3") (pintype "bidirectional"))
      (node (ref "J4") (pin "4") (pinfunction "4_4") (pintype "bidirectional"))
      (node (ref "J4") (pin "5") (pinfunction "5_5") (pintype "bidirectional"))
      (node (ref "J4") (pin "6") (pinfunction "6_6") (pintype "bidirectional"))
      (node (ref "J4") (pin "7") (pinfunction "7_7") (pintype "bidirectional"))
      (node (ref "J4") (pin "8") (pinfunction "8_8") (pintype "bidirectional"))
      (node (ref "J4") (pin "9") (pinfunction "9_9") (pintype "bidirectional"))
      (node (ref "J5") (pin "1") (pinfunction "1_1") (pintype "bidirectional"))
      (node (ref "J5") (pin "10") (pinfunction "10_10") (pintype "bidirectional"))
      (node (ref "J5") (pin "2") (pinfunction "2_2") (pintype "bidirectional"))
      (node (ref "J5") (pin "3") (pinfunction "3_3") (pintype "bidirectional"))
      (node (ref "J5") (pin "4") (pinfunction "4_4") (pintype "bidirectional"))
      (node (ref "J5") (pin "5") (pinfunction "5_5") (pintype "bidirectional"))
      (node (ref "J5") (pin "6") (pinfunction "6_6") (pintype "bidirectional"))
      (node (ref "J5") (pin "7") (pinfunction "7_7") (pintype "bidirectional"))
      (node (ref "J5") (pin "8") (pinfunction "8_8") (pintype "bidirectional"))
      (node (ref "J5") (pin "9") (pinfunction "9_9") (pintype "bidirectional"))
      (node (ref "J6") (pin "1") (pinfunction "1_1") (pintype "bidirectional"))
      (node (ref "J6") (pin "10") (pinfunction "10_10") (pintype "bidirectional"))
      (node (ref "J6") (pin "2") (pinfunction "2_2") (pintype "bidirectional"))
      (node (ref "J6") (pin "3") (pinfunction "3_3") (pintype "bidirectional"))
      (node (ref "J6") (pin "4") (pinfunction "4_4") (pintype "bidirectional"))
      (node (ref "J6") (pin "5") (pinfunction "5_5") (pintype "bidirectional"))
      (node (ref "J6") (pin "6") (pinfunction "6_6") (pintype "bidirectional"))
      (node (ref "J6") (pin "7") (pinfunction "7_7") (pintype "bidirectional"))
      (node (ref "J6") (pin "8") (pinfunction "8_8") (pintype "bidirectional"))
      (node (ref "J6") (pin "9") (pinfunction "9_9") (pintype "bidirectional"))
      (node (ref "R10") (pin "1") (pinfunction "1_1") (pintype "passive"))
      (node (ref "X4") (pin "1") (pinfunction "1_1") (pintype "passive"))
    )
    (net (code "4") (name "CAN1_RX") (class "Default")
      (node (ref "IC1") (pin "44") (pinfunction "PA11_44") (pintype "bidirectional"))
      (node (ref "IC3") (pin "4") (pinfunction "RXD_4") (pintype "bidirectional"))
      (node (ref "LED5") (pin "A") (pinfunction "A_A") (pintype "passive"))
    )
    (net (code "5") (name "CAN1_TX") (class "Default")
      (node (ref "IC1") (pin "45") (pinfunction "PA12_45") (pintype "bidirectional"))
      (node (ref "IC3") (pin "1") (pinfunction "TXD_1") (pintype "bidirectional"))
      (node (ref "LED4") (pin "A") (pinfunction "A_A") (pintype "passive"))
    )
    (net (code "6") (name "CANH") (class "Default")
      (node (ref "IC3") (pin "7") (pinfunction "CANH_7") (pintype "bidirectional"))
      (node (ref "J2") (pin "2") (pinfunction "2_2") (pintype "bidirectional"))
      (node (ref "J2") (pin "6") (pinfunction "6_6") (pintype "bidirectional"))
      (node (ref "R9") (pin "2") (pinfunction "2_2") (pintype "passive"))
    )
    (net (code "7") (name "CANL") (class "Default")
      (node (ref "IC3") (pin "6") (pinfunction "CANL_6") (pintype "bidirectional"))
      (node (ref "J2") (pin "3") (pinfunction "3_3") (pintype "bidirectional"))
      (node (ref "J2") (pin "7") (pinfunction "7_7") (pintype "bidirectional"))
      (node (ref "R9") (pin "1") (pinfunction "1_1") (pintype "passive"))
    )
    (net (code "8") (name "EN1A") (class "Default")
      (node (ref "IC1") (pin "41") (pinfunction "PA8_41") (pintype "bidirectional"))
      (node (ref "R54") (pin "1") (pinfunction "1_1") (pintype "passive"))
      (node (ref "X6") (pin "5") (pinfunction "5_5") (pintype "passive"))
    )
    (net (code "9") (name "EN1B") (class "Default")
      (node (ref "IC1") (pin "42") (pinfunction "PA9_42") (pintype "bidirectional"))
      (node (ref "R60") (pin "1") (pinfunction "1_1") (pintype "passive"))
      (node (ref "X6") (pin "3") (pinfunction "3_3") (pintype "passive"))
    )
    (net (code "10") (name "EN2A") (class "Default")
      (node (ref "IC1") (pin "37") (pinfunction "PC6_37") (pintype "bidirectional"))
      (node (ref "R66") (pin "1") (pinfunction "1_1") (pintype "passive"))
      (node (ref "X9") (pin "5") (pinfunction "5_5") (pintype "passive"))
    )
    (net (code "11") (name "EN2B") (class "Default")
      (node (ref "IC1") (pin "38") (pinfunction "PC7_38") (pintype "bidirectional"))
      (node (ref "R68") (pin "1") (pinfunction "1_1") (pintype "passive"))
      (node (ref "X9") (pin "3") (pinfunction "3_3") (pintype "passive"))
    )
    (net (code "12") (name "GND") (class "Default")
      (node (ref "C10") (pin "1") (pinfunction "1_1") (pintype "bidirectional"))
      (node (ref "C11") (pin "1") (pinfunction "1_1") (pintype "bidirectional"))
      (node (ref "C12") (pin "1") (pinfunction "1_1") (pintype "bidirectional"))
      (node (ref "C13") (pin "1") (pinfunction "1_1") (pintype "bidirectional"))
      (node (ref "C14") (pin "1") (pinfunction "1_1") (pintype "bidirectional"))
      (node (ref "C15") (pin "1") (pinfunction "1_1") (pintype "bidirectional"))
      (node (ref "C16") (pin "1") (pinfunction "1_1") (pintype "bidirectional"))
      (node (ref "C17") (pin "1") (pinfunction "1_1") (pintype "bidirectional"))
      (node (ref "C20") (pin "1") (pinfunction "1_1") (pintype "bidirectional"))
      (node (ref "C21") (pin "1") (pinfunction "1_1") (pintype "bidirectional"))
      (node (ref "C22") (pin "1") (pinfunction "1_1") (pintype "bidirectional"))
      (node (ref "C23") (pin "1") (pinfunction "1_1") (pintype "bidirectional"))
      (node (ref "C24") (pin "1") (pinfunction "1_1") (pintype "bidirectional"))
      (node (ref "C5") (pin "1") (pinfunction "1_1") (pintype "bidirectional"))
      (node (ref "C6") (pin "1") (pinfunction "1_1") (pintype "bidirectional"))
      (node (ref "C7") (pin "1") (pinfunction "1_1") (pintype "bidirectional"))
      (node (ref "C8") (pin "1") (pinfunction "1_1") (pintype "bidirectional"))
      (node (ref "C9") (pin "1") (pinfunction "1_1") (pintype "bidirectional"))
      (node (ref "IC1") (pin "12") (pinfunction "VSSA_12") (pintype "power_in"))
      (node (ref "IC1") (pin "18") (pinfunction "VSS_1_18") (pintype "power_in"))
      (node (ref "IC1") (pin "31") (pinfunction "VSS_2_31") (pintype "power_in"))
      (node (ref "IC1") (pin "47") (pinfunction "VSS_3_47") (pintype "power_in"))
      (node (ref "IC1") (pin "63") (pinfunction "VSS_4_63") (pintype "power_in"))
      (node (ref "IC3") (pin "2") (pinfunction "GND_2") (pintype "bidirectional"))
      (node (ref "IC3") (pin "8") (pinfunction "S_8") (pintype "bidirectional"))
      (node (ref "J2") (pin "4") (pinfunction "4_4") (pintype "bidirectional"))
      (node (ref "J2") (pin "8") (pinfunction "8_8") (pintype "bidirectional"))
      (node (ref "Q1") (pin "3") (pinfunction "C_3") (pintype "bidirectional"))
      (node (ref "Q10") (pin "3") (pinfunction "C_3") (pintype "bidirectional"))
      (node (ref "Q11") (pin "3") (pinfunction "C_3") (pintype "bidirectional"))
      (node (ref "Q15") (pin "3") (pinfunction "C_3") (pintype "bidirectional"))
      (node (ref "Q16") (pin "3") (pinfunction "C_3") (pintype "bidirectional"))
      (node (ref "Q2") (pin "3") (pinfunction "C_3") (pintype "bidirectional"))
      (node (ref "Q3") (pin "3") (pinfunction "C_3") (pintype "bidirectional"))
      (node (ref "Q4") (pin "3") (pinfunction "C_3") (pintype "bidirectional"))
      (node (ref "Q5") (pin "3") (pinfunction "C_3") (pintype "bidirectional"))
      (node (ref "Q7") (pin "3") (pinfunction "C_3") (pintype "bidirectional"))
      (node (ref "R1") (pin "1") (pinfunction "1_1") (pintype "passive"))
      (node (ref "R11") (pin "2") (pinfunction "2_2") (pintype "passive"))
      (node (ref "R12") (pin "2") (pinfunction "2_2") (pintype "passive"))
      (node (ref "R2") (pin "2") (pinfunction "2_2") (pintype "passive"))
      (node (ref "R3") (pin "2") (pinfunction "2_2") (pintype "passive"))
      (node (ref "R4") (pin "2") (pinfunction "2_2") (pintype "passive"))
      (node (ref "R5") (pin "2") (pinfunction "2_2") (pintype "passive"))
      (node (ref "R7") (pin "2") (pinfunction "2_2") (pintype "passive"))
      (node (ref "R8") (pin "2") (pinfunction "2_2") (pintype "passive"))
      (node (ref "S2") (pin "C1") (pinfunction "COM_1_C1") (pintype "bidirectional"))
      (node (ref "S2") (pin "D1") (pinfunction "COM_2_D1") (pintype "bidirectional"))
      (node (ref "SL1") (pin "3") (pinfunction "3_3") (pintype "passive"))
      (node (ref "TR11") (pin "2") (pinfunction "S_2") (pintype "bidirectional"))
      (node (ref "TR12") (pin "2") (pinfunction "S_2") (pintype "bidirectional"))
      (node (ref "TR15") (pin "2") (pinfunction "S_2") (pintype "bidirectional"))
      (node (ref "TR16") (pin "2") (pinfunction "S_2") (pintype "bidirectional"))
      (node (ref "TR19") (pin "2") (pinfunction "S_2") (pintype "bidirectional"))
      (node (ref "TR20") (pin "2") (pinfunction "S_2") (pintype "bidirectional"))
      (node (ref "TR21") (pin "2") (pinfunction "S_2") (pintype "bidirectional"))
      (node (ref "TR22") (pin "2") (pinfunction "S_2") (pintype "bidirectional"))
      (node (ref "TR25") (pin "2") (pinfunction "S_2") (pintype "bidirectional"))
      (node (ref "TR26") (pin "2") (pinfunction "S_2") (pintype "bidirectional"))
      (node (ref "TR6") (pin "2") (pinfunction "S_2") (pintype "bidirectional"))
      (node (ref "TR7") (pin "2") (pinfunction "S_2") (pintype "bidirectional"))
      (node (ref "TR8") (pin "2") (pinfunction "S_2") (pintype "bidirectional"))
      (node (ref "TR9") (pin "2") (pinfunction "S_2") (pintype "bidirectional"))
      (node (ref "U1") (pin "1") (pinfunction "GND_1") (pintype "passive"))
      (node (ref "X1") (pin "2") (pinfunction "2_2") (pintype "passive"))
      (node (ref "X3") (pin "3") (pinfunction "3_3") (pintype "passive"))
      (node (ref "X6") (pin "1") (pinfunction "1_1") (pintype "passive"))
      (node (ref "X9") (pin "1") (pinfunction "1_1") (pintype "passive"))
    )
    (net (code "13") (name "GND-M") (class "Default")
      (node (ref "C1") (pin "2") (pinfunction "-_2") (pintype "bidirectional"))
      (node (ref "C2") (pin "2") (pinfunction "-_2") (pintype "bidirectional"))
      (node (ref "C3") (pin "2") (pinfunction "-_2") (pintype "bidirectional"))
      (node (ref "C4") (pin "2") (pinfunction "-_2") (pintype "bidirectional"))
      (node (ref "J1") (pin "11") (pinfunction "11_11") (pintype "bidirectional"))
      (node (ref "J1") (pin "12") (pinfunction "12_12") (pintype "bidirectional"))
      (node (ref "J1") (pin "13") (pinfunction "13_13") (pintype "bidirectional"))
      (node (ref "J1") (pin "14") (pinfunction "14_14") (pintype "bidirectional"))
      (node (ref "J1") (pin "15") (pinfunction "15_15") (pintype "bidirectional"))
      (node (ref "J1") (pin "16") (pinfunction "16_16") (pintype "bidirectional"))
      (node (ref "J1") (pin "17") (pinfunction "17_17") (pintype "bidirectional"))
      (node (ref "J1") (pin "18") (pinfunction "18_18") (pintype "bidirectional"))
      (node (ref "J1") (pin "19") (pinfunction "19_19") (pintype "bidirectional"))
      (node (ref "J1") (pin "20") (pinfunction "20_20") (pintype "bidirectional"))
      (node (ref "J3") (pin "11") (pinfunction "11_11") (pintype "bidirectional"))
      (node (ref "J3") (pin "12") (pinfunction "12_12") (pintype "bidirectional"))
      (node (ref "J3") (pin "13") (pinfunction "13_13") (pintype "bidirectional"))
      (node (ref "J3") (pin "14") (pinfunction "14_14") (pintype "bidirectional"))
      (node (ref "J3") (pin "15") (pinfunction "15_15") (pintype "bidirectional"))
      (node (ref "J3") (pin "16") (pinfunction "16_16") (pintype "bidirectional"))
      (node (ref "J3") (pin "17") (pinfunction "17_17") (pintype "bidirectional"))
      (node (ref "J3") (pin "18") (pinfunction "18_18") (pintype "bidirectional"))
      (node (ref "J3") (pin "19") (pinfunction "19_19") (pintype "bidirectional"))
      (node (ref "J3") (pin "20") (pinfunction "20_20") (pintype "bidirectional"))
      (node (ref "J4") (pin "11") (pinfunction "11_11") (pintype "bidirectional"))
      (node (ref "J4") (pin "12") (pinfunction "12_12") (pintype "bidirectional"))
      (node (ref "J4") (pin "13") (pinfunction "13_13") (pintype "bidirectional"))
      (node (ref "J4") (pin "14") (pinfunction "14_14") (pintype "bidirectional"))
      (node (ref "J4") (pin "15") (pinfunction "15_15") (pintype "bidirectional"))
      (node (ref "J4") (pin "16") (pinfunction "16_16") (pintype "bidirectional"))
      (node (ref "J4") (pin "17") (pinfunction "17_17") (pintype "bidirectional"))
      (node (ref "J4") (pin "18") (pinfunction "18_18") (pintype "bidirectional"))
      (node (ref "J4") (pin "19") (pinfunction "19_19") (pintype "bidirectional"))
      (node (ref "J4") (pin "20") (pinfunction "20_20") (pintype "bidirectional"))
      (node (ref "J5") (pin "11") (pinfunction "11_11") (pintype "bidirectional"))
      (node (ref "J5") (pin "12") (pinfunction "12_12") (pintype "bidirectional"))
      (node (ref "J5") (pin "13") (pinfunction "13_13") (pintype "bidirectional"))
      (node (ref "J5") (pin "14") (pinfunction "14_14") (pintype "bidirectional"))
      (node (ref "J5") (pin "15") (pinfunction "15_15") (pintype "bidirectional"))
      (node (ref "J5") (pin "16") (pinfunction "16_16") (pintype "bidirectional"))
      (node (ref "J5") (pin "17") (pinfunction "17_17") (pintype "bidirectional"))
      (node (ref "J5") (pin "18") (pinfunction "18_18") (pintype "bidirectional"))
      (node (ref "J5") (pin "19") (pinfunction "19_19") (pintype "bidirectional"))
      (node (ref "J5") (pin "20") (pinfunction "20_20") (pintype "bidirectional"))
      (node (ref "J6") (pin "11") (pinfunction "11_11") (pintype "bidirectional"))
      (node (ref "J6") (pin "12") (pinfunction "12_12") (pintype "bidirectional"))
      (node (ref "J6") (pin "13") (pinfunction "13_13") (pintype "bidirectional"))
      (node (ref "J6") (pin "14") (pinfunction "14_14") (pintype "bidirectional"))
      (node (ref "J6") (pin "15") (pinfunction "15_15") (pintype "bidirectional"))
      (node (ref "J6") (pin "16") (pinfunction "16_16") (pintype "bidirectional"))
      (node (ref "J6") (pin "17") (pinfunction "17_17") (pintype "bidirectional"))
      (node (ref "J6") (pin "18") (pinfunction "18_18") (pintype "bidirectional"))
      (node (ref "J6") (pin "19") (pinfunction "19_19") (pintype "bidirectional"))
      (node (ref "J6") (pin "20") (pinfunction "20_20") (pintype "bidirectional"))
      (node (ref "LED1") (pin "K") (pinfunction "K_K") (pintype "passive"))
      (node (ref "X4") (pin "2") (pinfunction "2_2") (pintype "passive"))
    )
    (net (code "14") (name "I2C2_SCL") (class "Default")
      (node (ref "IC1") (pin "28") (pinfunction "PB10_28") (pintype "bidirectional"))
      (node (ref "X5") (pin "2") (pinfunction "2_2") (pintype "passive"))
    )
    (net (code "15") (name "I2C2_SDA") (class "Default")
      (node (ref "IC1") (pin "29") (pinfunction "PB11_29") (pintype "bidirectional"))
      (node (ref "X5") (pin "1") (pinfunction "1_1") (pintype "passive"))
    )
    (net (code "16") (name "MD1A") (class "Default")
      (node (ref "IC1") (pin "21") (pinfunction "PA5_21") (pintype "bidirectional"))
      (node (ref "R20") (pin "1") (pinfunction "1_1") (pintype "passive"))
      (node (ref "R21") (pin "1") (pinfunction "1_1") (pintype "passive"))
    )
    (net (code "17") (name "MD1B") (class "Default")
      (node (ref "IC1") (pin "55") (pinfunction "PB3_55") (pintype "bidirectional"))
      (node (ref "R23") (pin "1") (pinfunction "1_1") (pintype "passive"))
      (node (ref "R24") (pin "1") (pinfunction "1_1") (pintype "passive"))
    )
    (net (code "18") (name "MD2A") (class "Default")
      (node (ref "IC1") (pin "16") (pinfunction "PA2_16") (pintype "bidirectional"))
      (node (ref "R35") (pin "1") (pinfunction "1_1") (pintype "passive"))
      (node (ref "R36") (pin "1") (pinfunction "1_1") (pintype "passive"))
    )
    (net (code "19") (name "MD2B") (class "Default")
      (node (ref "IC1") (pin "17") (pinfunction "PA3_17") (pintype "bidirectional"))
      (node (ref "R38") (pin "1") (pinfunction "1_1") (pintype "passive"))
      (node (ref "R39") (pin "1") (pinfunction "1_1") (pintype "passive"))
    )
    (net (code "20") (name "MD3A") (class "Default")
      (node (ref "IC1") (pin "22") (pinfunction "PA6_22") (pintype "bidirectional"))
      (node (ref "R26") (pin "1") (pinfunction "1_1") (pintype "passive"))
      (node (ref "R27") (pin "1") (pinfunction "1_1") (pintype "passive"))
    )
    (net (code "21") (name "MD3B") (class "Default")
      (node (ref "IC1") (pin "23") (pinfunction "PA7_23") (pintype "bidirectional"))
      (node (ref "R29") (pin "1") (pinfunction "1_1") (pintype "passive"))
      (node (ref "R30") (pin "1") (pinfunction "1_1") (pintype "passive"))
    )
    (net (code "22") (name "MD4A") (class "Default")
      (node (ref "IC1") (pin "25") (pinfunction "PB0_25") (pintype "bidirectional"))
      (node (ref "R47") (pin "1") (pinfunction "1_1") (pintype "passive"))
      (node (ref "R48") (pin "1") (pinfunction "1_1") (pintype "passive"))
    )
    (net (code "23") (name "MD4B") (class "Default")
      (node (ref "IC1") (pin "26") (pinfunction "PB1_26") (pintype "bidirectional"))
      (node (ref "R50") (pin "1") (pinfunction "1_1") (pintype "passive"))
      (node (ref "R51") (pin "1") (pinfunction "1_1") (pintype "passive"))
    )
    (net (code "24") (name "MD5A") (class "Default")
      (node (ref "IC1") (pin "14") (pinfunction "PA0-WKUP_14") (pintype "bidirectional"))
      (node (ref "R63") (pin "1") (pinfunction "1_1") (pintype "passive"))
      (node (ref "R64") (pin "1") (pinfunction "1_1") (pintype "passive"))
    )
    (net (code "25") (name "MD5B") (class "Default")
      (node (ref "IC1") (pin "15") (pinfunction "PA1_15") (pintype "bidirectional"))
      (node (ref "R70") (pin "1") (pinfunction "1_1") (pintype "passive"))
      (node (ref "R71") (pin "1") (pinfunction "1_1") (pintype "passive"))
    )
    (net (code "26") (name "N$5") (class "Default")
      (node (ref "IC1") (pin "60") (pinfunction "BOOT0_60") (pintype "bidirectional"))
      (node (ref "R1") (pin "2") (pinfunction "2_2") (pintype "passive"))
    )
    (net (code "27") (name "NRST") (class "Default")
      (node (ref "C23") (pin "2") (pinfunction "2_2") (pintype "bidirectional"))
      (node (ref "IC1") (pin "7") (pinfunction "NRST_7") (pintype "bidirectional"))
      (node (ref "S2") (pin "A1") (pinfunction "NO_1_A1") (pintype "bidirectional"))
      (node (ref "SL1") (pin "5") (pinfunction "5_5") (pintype "passive"))
      (node (ref "X1") (pin "1") (pinfunction "1_1") (pintype "passive"))
    )
    (net (code "28") (name "Net-(LED1-PadA)") (class "Default")
      (node (ref "LED1") (pin "A") (pinfunction "A_A") (pintype "passive"))
      (node (ref "R10") (pin "2") (pinfunction "2_2") (pintype "passive"))
    )
    (net (code "29") (name "Net-(LED2-PadK)") (class "Default")
      (node (ref "LED2") (pin "K") (pinfunction "K_K") (pintype "passive"))
      (node (ref "R3") (pin "1") (pinfunction "1_1") (pintype "passive"))
    )
    (net (code "30") (name "Net-(LED3-PadK)") (class "Default")
      (node (ref "LED3") (pin "K") (pinfunction "K_K") (pintype "passive"))
      (node (ref "R4") (pin "1") (pinfunction "1_1") (pintype "passive"))
    )
    (net (code "31") (name "Net-(LED4-PadK)") (class "Default")
      (node (ref "LED4") (pin "K") (pinfunction "K_K") (pintype "passive"))
      (node (ref "R2") (pin "1") (pinfunction "1_1") (pintype "passive"))
    )
    (net (code "32") (name "Net-(LED5-PadK)") (class "Default")
      (node (ref "LED5") (pin "K") (pinfunction "K_K") (pintype "passive"))
      (node (ref "R5") (pin "1") (pinfunction "1_1") (pintype "passive"))
    )
    (net (code "33") (name "Net-(LED6-PadK)") (class "Default")
      (node (ref "LED6") (pin "K") (pinfunction "K_K") (pintype "passive"))
      (node (ref "R7") (pin "1") (pinfunction "1_1") (pintype "passive"))
    )
    (net (code "34") (name "Net-(LED7-PadK)") (class "Default")
      (node (ref "LED7") (pin "K") (pinfunction "K_K") (pintype "passive"))
      (node (ref "R8") (pin "1") (pinfunction "1_1") (pintype "passive"))
    )
    (net (code "35") (name "Net-(LED8-PadK)") (class "Default")
      (node (ref "LED8") (pin "K") (pinfunction "K_K") (pintype "passive"))
      (node (ref "R11") (pin "1") (pinfunction "1_1") (pintype "passive"))
    )
    (net (code "36") (name "Net-(LED9-PadK)") (class "Default")
      (node (ref "LED9") (pin "K") (pinfunction "K_K") (pintype "passive"))
      (node (ref "R12") (pin "1") (pinfunction "1_1") (pintype "passive"))
    )
    (net (code "37") (name "Net-(LED11-PadK)") (class "Default")
      (node (ref "LED11") (pin "K") (pinfunction "K_K") (pintype "passive"))
      (node (ref "R6") (pin "2") (pinfunction "2_2") (pintype "passive"))
    )
    (net (code "38") (name "Net-(LED12-PadK)") (class "Default")
      (node (ref "LED12") (pin "K") (pinfunction "K_K") (pintype "passive"))
      (node (ref "R22") (pin "2") (pinfunction "2_2") (pintype "passive"))
    )
    (net (code "39") (name "Net-(LED13-PadK)") (class "Default")
      (node (ref "LED13") (pin "K") (pinfunction "K_K") (pintype "passive"))
      (node (ref "R25") (pin "2") (pinfunction "2_2") (pintype "passive"))
    )
    (net (code "40") (name "Net-(LED14-PadK)") (class "Default")
      (node (ref "LED14") (pin "K") (pinfunction "K_K") (pintype "passive"))
      (node (ref "R28") (pin "2") (pinfunction "2_2") (pintype "passive"))
    )
    (net (code "41") (name "Net-(LED16-PadK)") (class "Default")
      (node (ref "LED16") (pin "K") (pinfunction "K_K") (pintype "passive"))
      (node (ref "R31") (pin "2") (pinfunction "2_2") (pintype "passive"))
    )
    (net (code "42") (name "Net-(LED17-PadK)") (class "Default")
      (node (ref "LED17") (pin "K") (pinfunction "K_K") (pintype "passive"))
      (node (ref "R37") (pin "2") (pinfunction "2_2") (pintype "passive"))
    )
    (net (code "43") (name "Net-(LED20-PadK)") (class "Default")
      (node (ref "LED20") (pin "K") (pinfunction "K_K") (pintype "passive"))
      (node (ref "R46") (pin "2") (pinfunction "2_2") (pintype "passive"))
    )
    (net (code "44") (name "Net-(LED21-PadK)") (class "Default")
      (node (ref "LED21") (pin "K") (pinfunction "K_K") (pintype "passive"))
      (node (ref "R49") (pin "2") (pinfunction "2_2") (pintype "passive"))
    )
    (net (code "45") (name "Net-(LED24-PadA)") (class "Default")
      (node (ref "LED24") (pin "A") (pinfunction "A_A") (pintype "passive"))
      (node (ref "R59") (pin "2") (pinfunction "2_2") (pintype "passive"))
    )
    (net (code "46") (name "Net-(LED25-PadA)") (class "Default")
      (node (ref "LED25") (pin "A") (pinfunction "A_A") (pintype "passive"))
      (node (ref "R61") (pin "2") (pinfunction "2_2") (pintype "passive"))
    )
    (net (code "47") (name "Net-(LED26-PadK)") (class "Default")
      (node (ref "LED26") (pin "K") (pinfunction "K_K") (pintype "passive"))
      (node (ref "R62") (pin "2") (pinfunction "2_2") (pintype "passive"))
    )
    (net (code "48") (name "Net-(LED27-PadK)") (class "Default")
      (node (ref "LED27") (pin "K") (pinfunction "K_K") (pintype "passive"))
      (node (ref "R65") (pin "2") (pinfunction "2_2") (pintype "passive"))
    )
    (net (code "49") (name "Net-(LED30-PadA)") (class "Default")
      (node (ref "LED30") (pin "A") (pinfunction "A_A") (pintype "passive"))
      (node (ref "R67") (pin "2") (pinfunction "2_2") (pintype "passive"))
    )
    (net (code "50") (name "Net-(LED31-PadA)") (class "Default")
      (node (ref "LED31") (pin "A") (pinfunction "A_A") (pintype "passive"))
      (node (ref "R69") (pin "2") (pinfunction "2_2") (pintype "passive"))
    )
    (net (code "51") (name "Net-(Q1-B)") (class "Default")
      (node (ref "Q1") (pin "1") (pinfunction "B_1") (pintype "bidirectional"))
      (node (ref "R24") (pin "2") (pinfunction "2_2") (pintype "passive"))
    )
    (net (code "52") (name "Net-(Q2-B)") (class "Default")
      (node (ref "Q2") (pin "1") (pinfunction "B_1") (pintype "bidirectional"))
      (node (ref "R21") (pin "2") (pinfunction "2_2") (pintype "passive"))
    )
    (net (code "53") (name "Net-(Q3-B)") (class "Default")
      (node (ref "Q3") (pin "1") (pinfunction "B_1") (pintype "bidirectional"))
      (node (ref "R30") (pin "2") (pinfunction "2_2") (pintype "passive"))
    )
    (net (code "54") (name "Net-(Q4-B)") (class "Default")
      (node (ref "Q4") (pin "1") (pinfunction "B_1") (pintype "bidirectional"))
      (node (ref "R27") (pin "2") (pinfunction "2_2") (pintype "passive"))
    )
    (net (code "55") (name "Net-(Q5-B)") (class "Default")
      (node (ref "Q5") (pin "1") (pinfunction "B_1") (pintype "bidirectional"))
      (node (ref "R39") (pin "2") (pinfunction "2_2") (pintype "passive"))
    )
    (net (code "56") (name "Net-(Q7-B)") (class "Default")
      (node (ref "Q7") (pin "1") (pinfunction "B_1") (pintype "bidirectional"))
      (node (ref "R36") (pin "2") (pinfunction "2_2") (pintype "passive"))
    )
    (net (code "57") (name "Net-(Q10-B)") (class "Default")
      (node (ref "Q10") (pin "1") (pinfunction "B_1") (pintype "bidirectional"))
      (node (ref "R51") (pin "2") (pinfunction "2_2") (pintype "passive"))
    )
    (net (code "58") (name "Net-(Q11-B)") (class "Default")
      (node (ref "Q11") (pin "1") (pinfunction "B_1") (pintype "bidirectional"))
      (node (ref "R48") (pin "2") (pinfunction "2_2") (pintype "passive"))
    )
    (net (code "59") (name "Net-(Q15-B)") (class "Default")
      (node (ref "Q15") (pin "1") (pinfunction "B_1") (pintype "bidirectional"))
      (node (ref "R71") (pin "2") (pinfunction "2_2") (pintype "passive"))
    )
    (net (code "60") (name "Net-(Q16-B)") (class "Default")
      (node (ref "Q16") (pin "1") (pinfunction "B_1") (pintype "bidirectional"))
      (node (ref "R64") (pin "2") (pinfunction "2_2") (pintype "passive"))
    )
    (net (code "61") (name "Net-(TR6-D)") (class "Default")
      (node (ref "R6") (pin "1") (pinfunction "1_1") (pintype "passive"))
      (node (ref "TR6") (pin "3") (pinfunction "D_3") (pintype "bidirectional"))
    )
    (net (code "62") (name "Net-(TR6-G)") (class "Default")
      (node (ref "R20") (pin "2") (pinfunction "2_2") (pintype "passive"))
      (node (ref "TR6") (pin "1") (pinfunction "G_1") (pintype "bidirectional"))
    )
    (net (code "63") (name "Net-(TR7-D)") (class "Default")
      (node (ref "R22") (pin "1") (pinfunction "1_1") (pintype "passive"))
      (node (ref "TR7") (pin "3") (pinfunction "D_3") (pintype "bidirectional"))
    )
    (net (code "64") (name "Net-(TR7-G)") (class "Default")
      (node (ref "R23") (pin "2") (pinfunction "2_2") (pintype "passive"))
      (node (ref "TR7") (pin "1") (pinfunction "G_1") (pintype "bidirectional"))
    )
    (net (code "65") (name "Net-(TR8-D)") (class "Default")
      (node (ref "R25") (pin "1") (pinfunction "1_1") (pintype "passive"))
      (node (ref "TR8") (pin "3") (pinfunction "D_3") (pintype "bidirectional"))
    )
    (net (code "66") (name "Net-(TR8-G)") (class "Default")
      (node (ref "R26") (pin "2") (pinfunction "2_2") (pintype "passive"))
      (node (ref "TR8") (pin "1") (pinfunction "G_1") (pintype "bidirectional"))
    )
    (net (code "67") (name "Net-(TR9-D)") (class "Default")
      (node (ref "R28") (pin "1") (pinfunction "1_1") (pintype "passive"))
      (node (ref "TR9") (pin "3") (pinfunction "D_3") (pintype "bidirectional"))
    )
    (net (code "68") (name "Net-(TR9-G)") (class "Default")
      (node (ref "R29") (pin "2") (pinfunction "2_2") (pintype "passive"))
      (node (ref "TR9") (pin "1") (pinfunction "G_1") (pintype "bidirectional"))
    )
    (net (code "69") (name "Net-(TR11-D)") (class "Default")
      (node (ref "R31") (pin "1") (pinfunction "1_1") (pintype "passive"))
      (node (ref "TR11") (pin "3") (pinfunction "D_3") (pintype "bidirectional"))
    )
    (net (code "70") (name "Net-(TR11-G)") (class "Default")
      (node (ref "R35") (pin "2") (pinfunction "2_2") (pintype "passive"))
      (node (ref "TR11") (pin "1") (pinfunction "G_1") (pintype "bidirectional"))
    )
    (net (code "71") (name "Net-(TR12-D)") (class "Default")
      (node (ref "R37") (pin "1") (pinfunction "1_1") (pintype "passive"))
      (node (ref "TR12") (pin "3") (pinfunction "D_3") (pintype "bidirectional"))
    )
    (net (code "72") (name "Net-(TR12-G)") (class "Default")
      (node (ref "R38") (pin "2") (pinfunction "2_2") (pintype "passive"))
      (node (ref "TR12") (pin "1") (pinfunction "G_1") (pintype "bidirectional"))
    )
    (net (code "73") (name "Net-(TR15-D)") (class "Default")
      (node (ref "R46") (pin "1") (pinfunction "1_1") (pintype "passive"))
      (node (ref "TR15") (pin "3") (pinfunction "D_3") (pintype "bidirectional"))
    )
    (net (code "74") (name "Net-(TR15-G)") (class "Default")
      (node (ref "R47") (pin "2") (pinfunction "2_2") (pintype "passive"))
      (node (ref "TR15") (pin "1") (pinfunction "G_1") (pintype "bidirectional"))
    )
    (net (code "75") (name "Net-(TR16-D)") (class "Default")
      (node (ref "R49") (pin "1") (pinfunction "1_1") (pintype "passive"))
      (node (ref "TR16") (pin "3") (pinfunction "D_3") (pintype "bidirectional"))
    )
    (net (code "76") (name "Net-(TR16-G)") (class "Default")
      (node (ref "R50") (pin "2") (pinfunction "2_2") (pintype "passive"))
      (node (ref "TR16") (pin "1") (pinfunction "G_1") (pintype "bidirectional"))
    )
    (net (code "77") (name "Net-(TR19-D)") (class "Default")
      (node (ref "R62") (pin "1") (pinfunction "1_1") (pintype "passive"))
      (node (ref "TR19") (pin "3") (pinfunction "D_3") (pintype "bidirectional"))
    )
    (net (code "78") (name "Net-(TR19-G)") (class "Default")
      (node (ref "R63") (pin "2") (pinfunction "2_2") (pintype "passive"))
      (node (ref "TR19") (pin "1") (pinfunction "G_1") (pintype "bidirectional"))
    )
    (net (code "79") (name "Net-(TR20-D)") (class "Default")
      (node (ref "R65") (pin "1") (pinfunction "1_1") (pintype "passive"))
      (node (ref "TR20") (pin "3") (pinfunction "D_3") (pintype "bidirectional"))
    )
    (net (code "80") (name "Net-(TR20-G)") (class "Default")
      (node (ref "R70") (pin "2") (pinfunction "2_2") (pintype "passive"))
      (node (ref "TR20") (pin "1") (pinfunction "G_1") (pintype "bidirectional"))
    )
    (net (code "81") (name "Net-(TR21-D)") (class "Default")
      (node (ref "LED25") (pin "K") (pinfunction "K_K") (pintype "passive"))
      (node (ref "TR21") (pin "3") (pinfunction "D_3") (pintype "bidirectional"))
    )
    (net (code "82") (name "Net-(TR21-G)") (class "Default")
      (node (ref "R60") (pin "2") (pinfunction "2_2") (pintype "passive"))
      (node (ref "TR21") (pin "1") (pinfunction "G_1") (pintype "bidirectional"))
    )
    (net (code "83") (name "Net-(TR22-D)") (class "Default")
      (node (ref "LED24") (pin "K") (pinfunction "K_K") (pintype "passive"))
      (node (ref "TR22") (pin "3") (pinfunction "D_3") (pintype "bidirectional"))
    )
    (net (code "84") (name "Net-(TR22-G)") (class "Default")
      (node (ref "R54") (pin "2") (pinfunction "2_2") (pintype "passive"))
      (node (ref "TR22") (pin "1") (pinfunction "G_1") (pintype "bidirectional"))
    )
    (net (code "85") (name "Net-(TR25-D)") (class "Default")
      (node (ref "LED31") (pin "K") (pinfunction "K_K") (pintype "passive"))
      (node (ref "TR25") (pin "3") (pinfunction "D_3") (pintype "bidirectional"))
    )
    (net (code "86") (name "Net-(TR25-G)") (class "Default")
      (node (ref "R68") (pin "2") (pinfunction "2_2") (pintype "passive"))
      (node (ref "TR25") (pin "1") (pinfunction "G_1") (pintype "bidirectional"))
    )
    (net (code "87") (name "Net-(TR26-D)") (class "Default")
      (node (ref "LED30") (pin "K") (pinfunction "K_K") (pintype "passive"))
      (node (ref "TR26") (pin "3") (pinfunction "D_3") (pintype "bidirectional"))
    )
    (net (code "88") (name "Net-(TR26-G)") (class "Default")
      (node (ref "R66") (pin "2") (pinfunction "2_2") (pintype "passive"))
      (node (ref "TR26") (pin "1") (pinfunction "G_1") (pintype "bidirectional"))
    )
    (net (code "89") (name "PA0") (class "Default")
      (node (ref "J6") (pin "25") (pinfunction "25_25") (pintype "bidirectional"))
      (node (ref "J6") (pin "26") (pinfunction "26_26") (pintype "bidirectional"))
      (node (ref "Q16") (pin "2") (pinfunction "E_2") (pintype "bidirectional"))
    )
    (net (code "90") (name "PA1") (class "Default")
      (node (ref "J6") (pin "23") (pinfunction "23_23") (pintype "bidirectional"))
      (node (ref "J6") (pin "24") (pinfunction "24_24") (pintype "bidirectional"))
      (node (ref "Q15") (pin "2") (pinfunction "E_2") (pintype "bidirectional"))
    )
    (net (code "91") (name "PA2") (class "Default")
      (node (ref "J3") (pin "25") (pinfunction "25_25") (pintype "bidirectional"))
      (node (ref "J3") (pin "26") (pinfunction "26_26") (pintype "bidirectional"))
      (node (ref "Q7") (pin "2") (pinfunction "E_2") (pintype "bidirectional"))
    )
    (net (code "92") (name "PA3") (class "Default")
      (node (ref "J3") (pin "23") (pinfunction "23_23") (pintype "bidirectional"))
      (node (ref "J3") (pin "24") (pinfunction "24_24") (pintype "bidirectional"))
      (node (ref "Q5") (pin "2") (pinfunction "E_2") (pintype "bidirectional"))
    )
    (net (code "93") (name "PA5") (class "Default")
      (node (ref "J1") (pin "25") (pinfunction "25_25") (pintype "bidirectional"))
      (node (ref "J1") (pin "26") (pinfunction "26_26") (pintype "bidirectional"))
      (node (ref "Q2") (pin "2") (pinfunction "E_2") (pintype "bidirectional"))
    )
    (net (code "94") (name "PA6") (class "Default")
      (node (ref "J4") (pin "25") (pinfunction "25_25") (pintype "bidirectional"))
      (node (ref "J4") (pin "26") (pinfunction "26_26") (pintype "bidirectional"))
      (node (ref "Q4") (pin "2") (pinfunction "E_2") (pintype "bidirectional"))
    )
    (net (code "95") (name "PA7") (class "Default")
      (node (ref "J4") (pin "23") (pinfunction "23_23") (pintype "bidirectional"))
      (node (ref "J4") (pin "24") (pinfunction "24_24") (pintype "bidirectional"))
      (node (ref "Q3") (pin "2") (pinfunction "E_2") (pintype "bidirectional"))
    )
    (net (code "96") (name "PB0") (class "Default")
      (node (ref "J5") (pin "25") (pinfunction "25_25") (pintype "bidirectional"))
      (node (ref "J5") (pin "26") (pinfunction "26_26") (pintype "bidirectional"))
      (node (ref "Q11") (pin "2") (pinfunction "E_2") (pintype "bidirectional"))
    )
    (net (code "97") (name "PB1") (class "Default")
      (node (ref "J5") (pin "23") (pinfunction "23_23") (pintype "bidirectional"))
      (node (ref "J5") (pin "24") (pinfunction "24_24") (pintype "bidirectional"))
      (node (ref "Q10") (pin "2") (pinfunction "E_2") (pintype "bidirectional"))
    )
    (net (code "98") (name "PB3") (class "Default")
      (node (ref "J1") (pin "23") (pinfunction "23_23") (pintype "bidirectional"))
      (node (ref "J1") (pin "24") (pinfunction "24_24") (pintype "bidirectional"))
      (node (ref "Q1") (pin "2") (pinfunction "E_2") (pintype "bidirectional"))
    )
    (net (code "99") (name "PB12") (class "Default")
      (node (ref "IC1") (pin "33") (pinfunction "PB12_33") (pintype "bidirectional"))
      (node (ref "JP1") (pin "5") (pinfunction "5_5") (pintype "passive"))
    )
    (net (code "100") (name "PB13") (class "Default")
      (node (ref "IC1") (pin "34") (pinfunction "PB13_34") (pintype "bidirectional"))
      (node (ref "JP1") (pin "3") (pinfunction "3_3") (pintype "passive"))
    )
    (net (code "101") (name "PB14") (class "Default")
      (node (ref "IC1") (pin "35") (pinfunction "PB14_35") (pintype "bidirectional"))
      (node (ref "JP1") (pin "1") (pinfunction "1_1") (pintype "passive"))
    )
    (net (code "102") (name "PC1") (class "Default")
      (node (ref "IC1") (pin "9") (pinfunction "PC1_9") (pintype "bidirectional"))
      (node (ref "JP1") (pin "6") (pinfunction "6_6") (pintype "passive"))
    )
    (net (code "103") (name "PC2") (class "Default")
      (node (ref "IC1") (pin "10") (pinfunction "PC2_10") (pintype "bidirectional"))
      (node (ref "JP1") (pin "4") (pinfunction "4_4") (pintype "passive"))
    )
    (net (code "104") (name "PC3") (class "Default")
      (node (ref "IC1") (pin "11") (pinfunction "PC3_11") (pintype "bidirectional"))
      (node (ref "JP1") (pin "2") (pinfunction "2_2") (pintype "passive"))
    )
    (net (code "105") (name "PC14") (class "Default")
      (node (ref "IC1") (pin "3") (pinfunction "PC14-OSC32_IN_3") (pintype "bidirectional"))
      (node (ref "LED9") (pin "A") (pinfunction "A_A") (pintype "passive"))
    )
    (net (code "106") (name "PC15") (class "Default")
      (node (ref "IC1") (pin "4") (pinfunction "PC15-OSC32_OUT_4") (pintype "bidirectional"))
      (node (ref "LED8") (pin "A") (pinfunction "A_A") (pintype "passive"))
    )
    (net (code "107") (name "PH0") (class "Default")
      (node (ref "IC1") (pin "5") (pinfunction "PH0-OSC_IN_5") (pintype "bidirectional"))
      (node (ref "LED7") (pin "A") (pinfunction "A_A") (pintype "passive"))
    )
    (net (code "108") (name "PH1") (class "Default")
      (node (ref "IC1") (pin "6") (pinfunction "PH1-OSC_OUT_6") (pintype "bidirectional"))
      (node (ref "LED6") (pin "A") (pinfunction "A_A") (pintype "passive"))
    )
    (net (code "109") (name "SPI3_MISO") (class "Default")
      (node (ref "IC1") (pin "52") (pinfunction "PC11_52") (pintype "bidirectional"))
      (node (ref "X7") (pin "2") (pinfunction "2_2") (pintype "passive"))
    )
    (net (code "110") (name "SPI3_MOSI") (class "Default")
      (node (ref "IC1") (pin "53") (pinfunction "PC12_53") (pintype "bidirectional"))
      (node (ref "X7") (pin "1") (pinfunction "1_1") (pintype "passive"))
    )
    (net (code "111") (name "SPI3_NSS") (class "Default")
      (node (ref "IC1") (pin "50") (pinfunction "PA15_50") (pintype "bidirectional"))
      (node (ref "X7") (pin "4") (pinfunction "4_4") (pintype "passive"))
    )
    (net (code "112") (name "SPI3_SCK") (class "Default")
      (node (ref "IC1") (pin "51") (pinfunction "PC10_51") (pintype "bidirectional"))
      (node (ref "X7") (pin "3") (pinfunction "3_3") (pintype "passive"))
    )
    (net (code "113") (name "SWCLK") (class "Default")
      (node (ref "IC1") (pin "49") (pinfunction "PA14_49") (pintype "bidirectional"))
      (node (ref "SL1") (pin "2") (pinfunction "2_2") (pintype "passive"))
    )
    (net (code "114") (name "SWDIO") (class "Default")
      (node (ref "IC1") (pin "46") (pinfunction "PA13_46") (pintype "bidirectional"))
      (node (ref "SL1") (pin "4") (pinfunction "4_4") (pintype "passive"))
    )
    (net (code "115") (name "USART1_RX") (class "Default")
      (node (ref "IC1") (pin "59") (pinfunction "PB7_59") (pintype "bidirectional"))
      (node (ref "X2") (pin "2") (pinfunction "2_2") (pintype "passive"))
    )
    (net (code "116") (name "USART1_TX") (class "Default")
      (node (ref "IC1") (pin "58") (pinfunction "PB6_58") (pintype "bidirectional"))
      (node (ref "X2") (pin "1") (pinfunction "1_1") (pintype "passive"))
    )
    (net (code "117") (name "unconnected-(IC1-PA4-Pad20)") (class "Default")
      (node (ref "IC1") (pin "20") (pinfunction "PA4_20") (pintype "bidirectional"))
    )
    (net (code "118") (name "unconnected-(IC1-PA10-Pad43)") (class "Default")
      (node (ref "IC1") (pin "43") (pinfunction "PA10_43") (pintype "bidirectional"))
    )
    (net (code "119") (name "unconnected-(IC1-PB2-Pad27)") (class "Default")
      (node (ref "IC1") (pin "27") (pinfunction "PB2_27") (pintype "bidirectional"))
    )
    (net (code "120") (name "unconnected-(IC1-PB4-Pad56)") (class "Default")
      (node (ref "IC1") (pin "56") (pinfunction "PB4_56") (pintype "bidirectional"))
    )
    (net (code "121") (name "unconnected-(IC1-PB5-Pad57)") (class "Default")
      (node (ref "IC1") (pin "57") (pinfunction "PB5_57") (pintype "bidirectional"))
    )
    (net (code "122") (name "unconnected-(IC1-PB8-Pad61)") (class "Default")
      (node (ref "IC1") (pin "61") (pinfunction "PB8_61") (pintype "bidirectional"))
    )
    (net (code "123") (name "unconnected-(IC1-PB9-Pad62)") (class "Default")
      (node (ref "IC1") (pin "62") (pinfunction "PB9_62") (pintype "bidirectional"))
    )
    (net (code "124") (name "unconnected-(IC1-PB15-Pad36)") (class "Default")
      (node (ref "IC1") (pin "36") (pinfunction "PB15_36") (pintype "bidirectional"))
    )
    (net (code "125") (name "unconnected-(IC1-PC0-Pad8)") (class "Default")
      (node (ref "IC1") (pin "8") (pinfunction "PC0_8") (pintype "bidirectional"))
    )
    (net (code "126") (name "unconnected-(IC1-PC4-Pad24)") (class "Default")
      (node (ref "IC1") (pin "24") (pinfunction "PC4_24") (pintype "bidirectional"))
    )
    (net (code "127") (name "unconnected-(IC1-PC8-Pad39)") (class "Default")
      (node (ref "IC1") (pin "39") (pinfunction "PC8_39") (pintype "bidirectional"))
    )
    (net (code "128") (name "unconnected-(IC1-PC9-Pad40)") (class "Default")
      (node (ref "IC1") (pin "40") (pinfunction "PC9_40") (pintype "bidirectional"))
    )
    (net (code "129") (name "unconnected-(IC1-PC13-Pad2)") (class "Default")
      (node (ref "IC1") (pin "2") (pinfunction "PC13_2") (pintype "bidirectional"))
    )
    (net (code "130") (name "unconnected-(IC1-PD2-Pad54)") (class "Default")
      (node (ref "IC1") (pin "54") (pinfunction "PD2_54") (pintype "bidirectional"))
    )
    (net (code "131") (name "unconnected-(J2-PadMH1)") (class "Default")
      (node (ref "J2") (pin "MH1") (pinfunction "MH1_MH1") (pintype "bidirectional"))
    )
    (net (code "132") (name "unconnected-(J2-PadMH2)") (class "Default")
      (node (ref "J2") (pin "MH2") (pinfunction "MH2_MH2") (pintype "bidirectional"))
    )
    (net (code "133") (name "unconnected-(J2-PadMH3)") (class "Default")
      (node (ref "J2") (pin "MH3") (pinfunction "MH3_MH3") (pintype "bidirectional"))
    )
    (net (code "134") (name "unconnected-(J2-PadMH4)") (class "Default")
      (node (ref "J2") (pin "MH4") (pinfunction "MH4_MH4") (pintype "bidirectional"))
    )
    (net (code "135") (name "unconnected-(S2-NO_2-PadB1)") (class "Default")
      (node (ref "S2") (pin "B1") (pinfunction "NO_2_B1") (pintype "bidirectional"))
    )
    (net (code "136") (name "unconnected-(SL1-Pad6)") (class "Default")
      (node (ref "SL1") (pin "6") (pinfunction "6_6") (pintype "passive"))
    )
    (net (code "137") (name "unconnected-(X6-Pad2)") (class "Default")
      (node (ref "X6") (pin "2") (pinfunction "2_2") (pintype "passive"))
    )
    (net (code "138") (name "unconnected-(X9-Pad2)") (class "Default")
      (node (ref "X9") (pin "2") (pinfunction "2_2") (pintype "passive"))
    )
  )
)
